# unitbase_Exodia.net
KiCad netlist of a schematic drawn in EAGLE
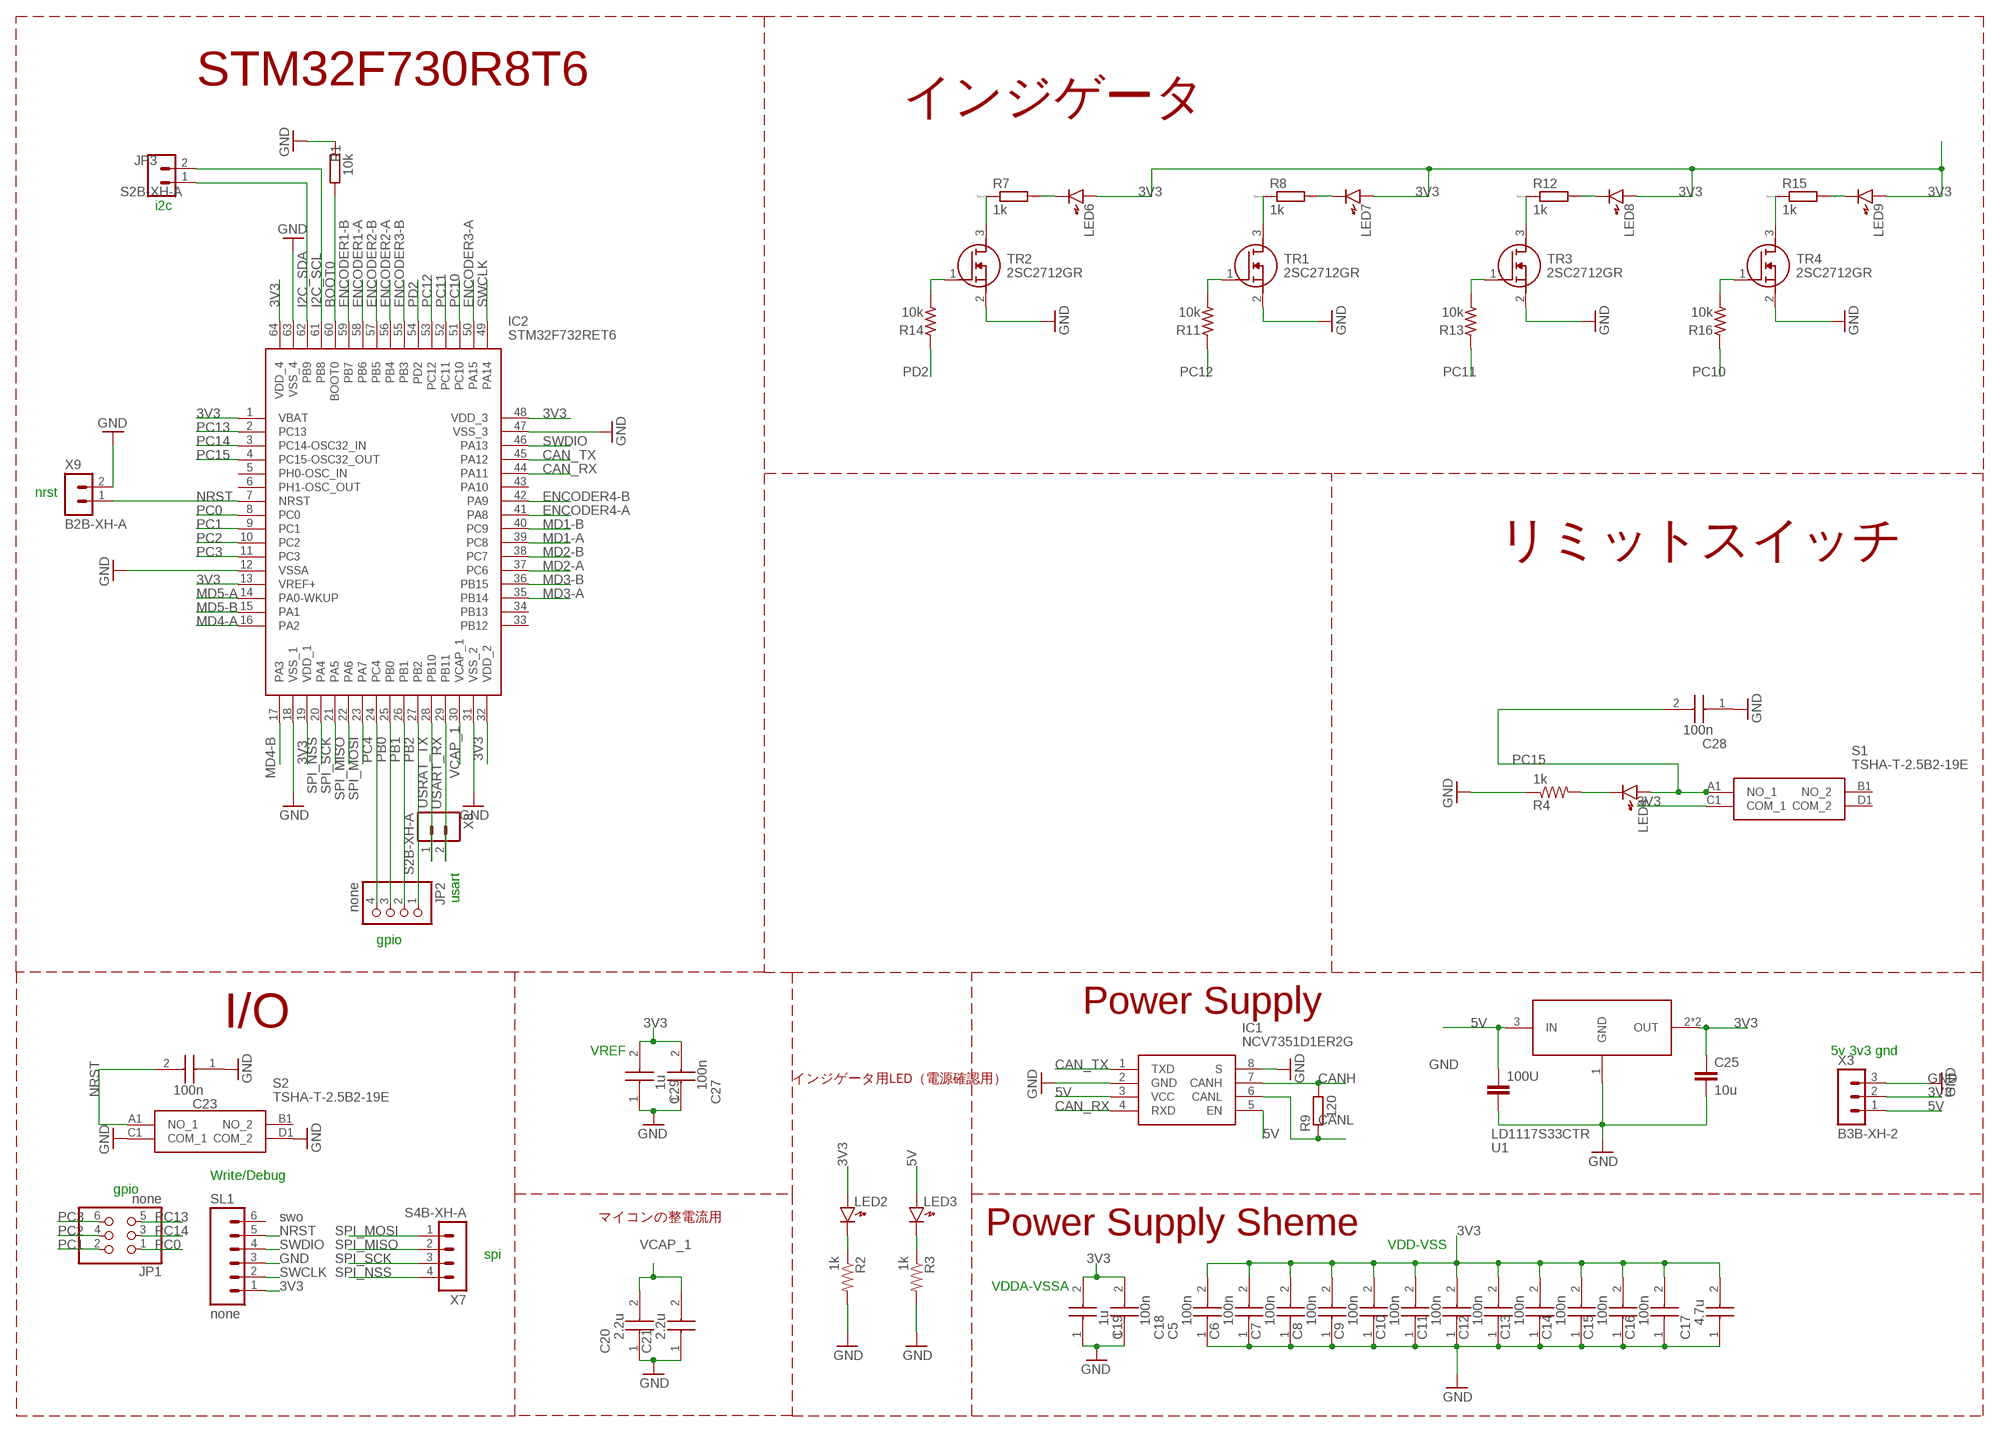
[diagram p0: schematic, sheet 1]
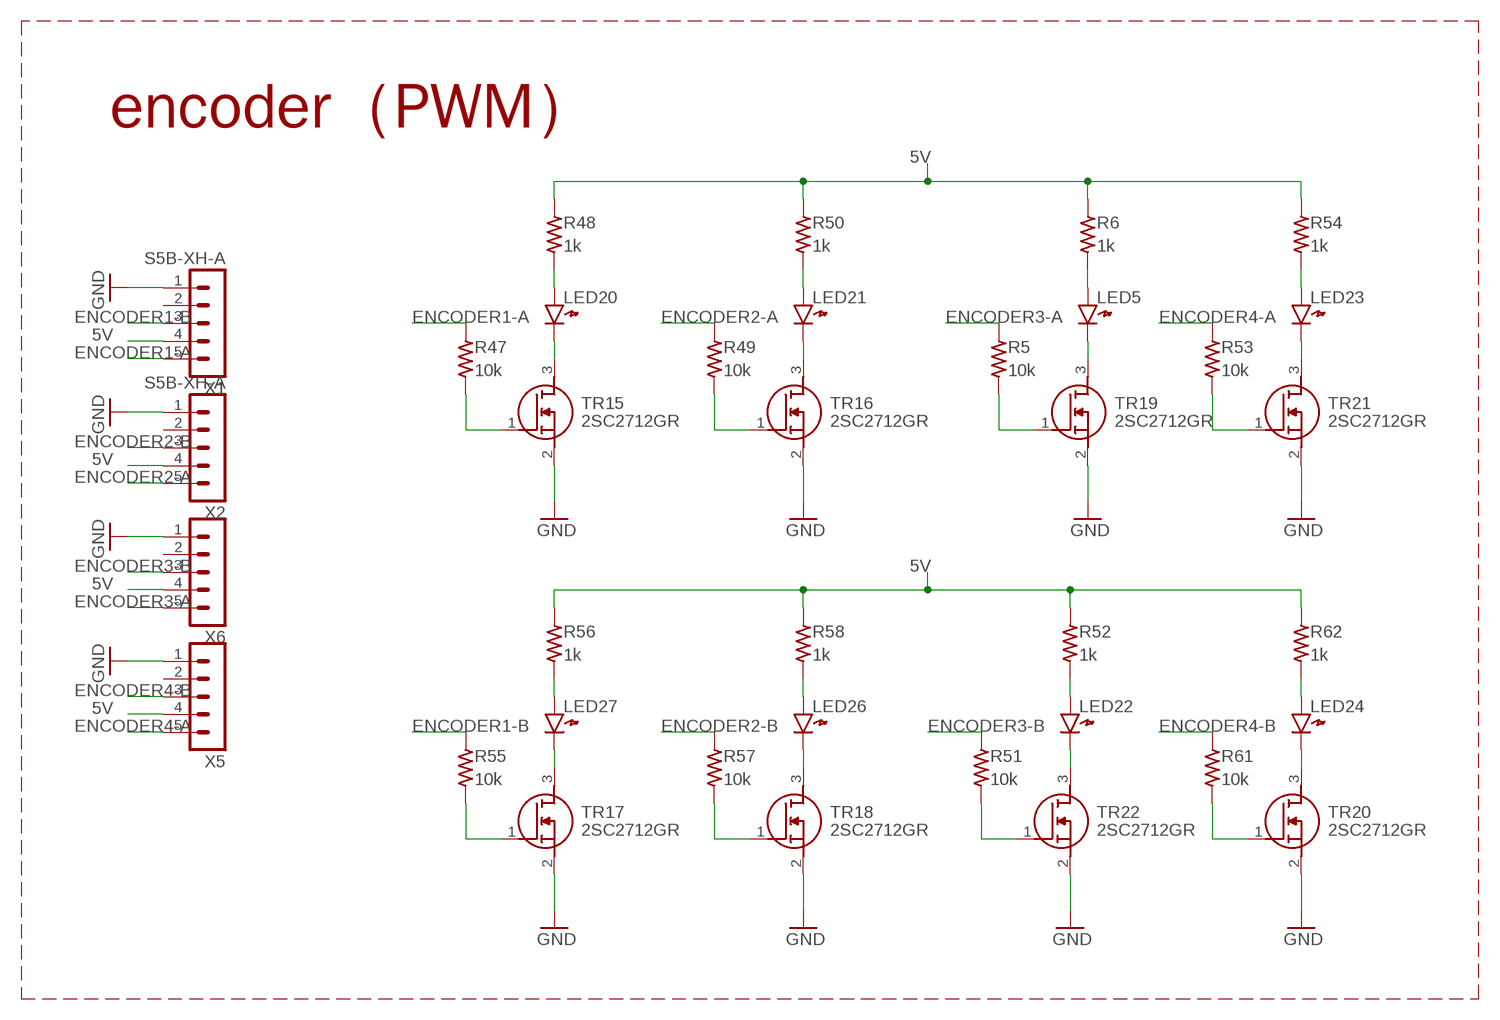
[diagram p1: schematic, sheet 2]
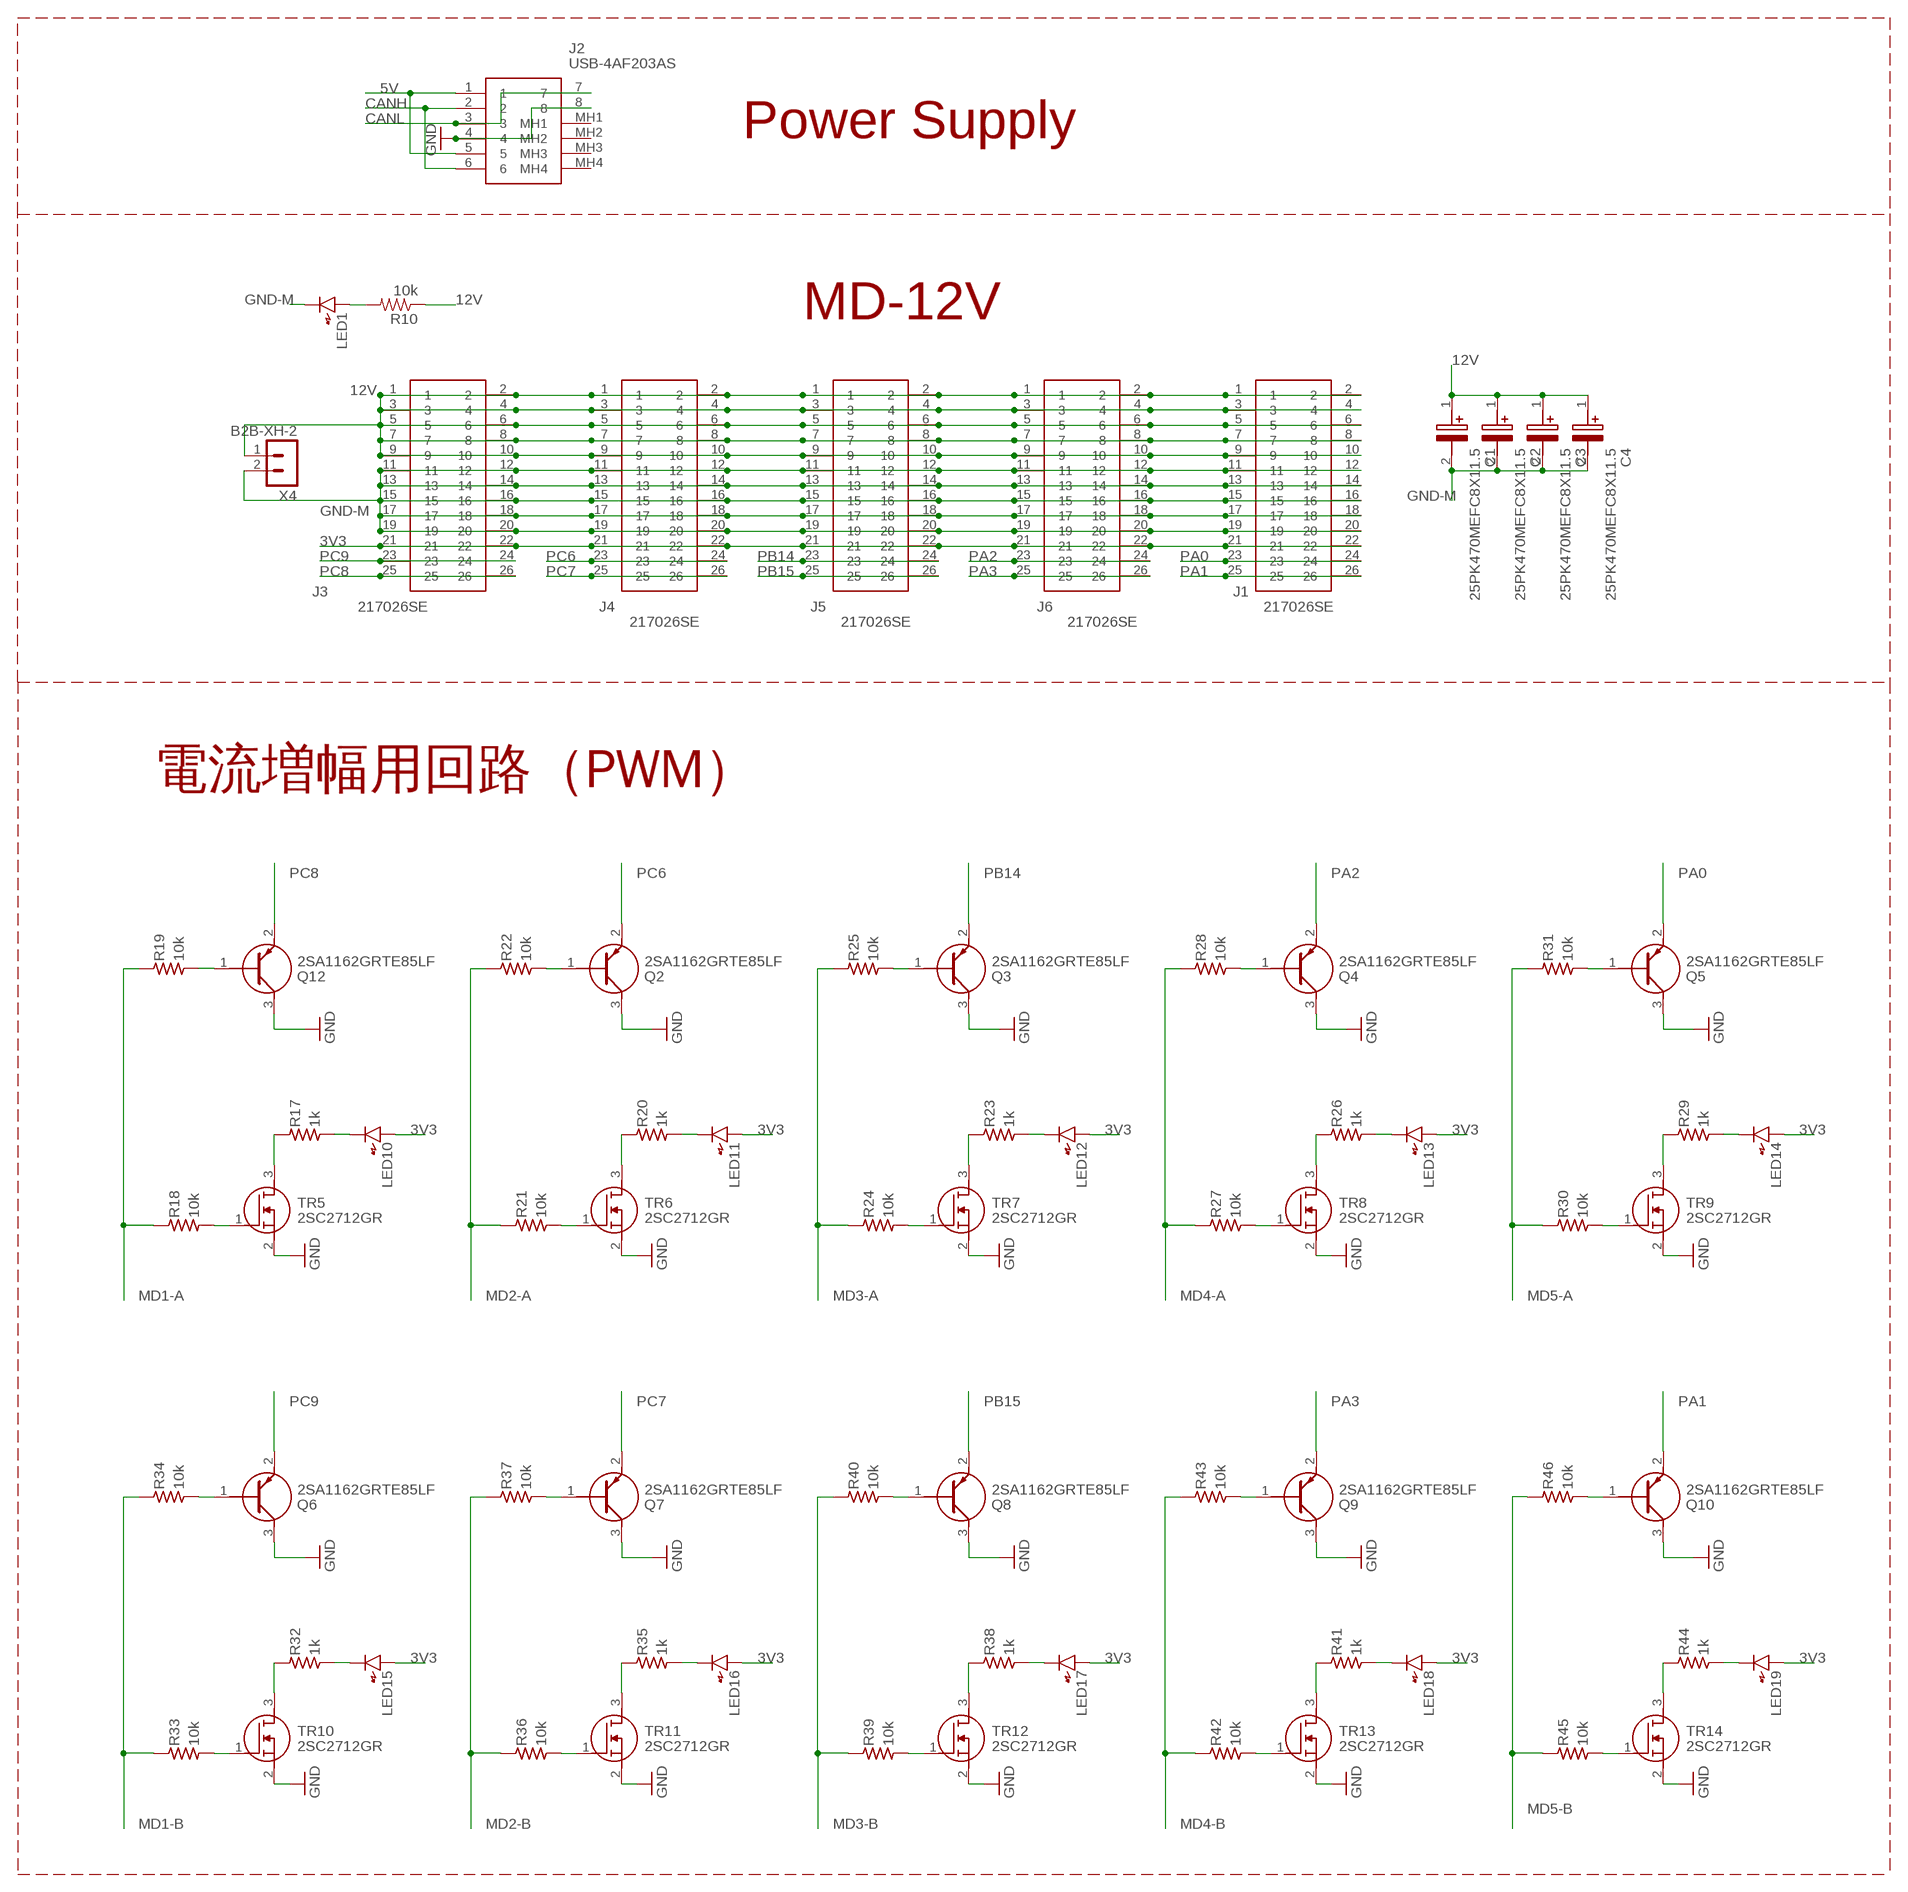
[diagram p2: schematic, sheet 3]

(export (version "E")
  (design (tool "Eeschema 10.0.6"))
  (components
    (comp (ref "LED5")
      (value "LED1608")
      (footprint "eagle-import:LED1608")
      (libsource (lib "eagle-import") (part "LED1608"))
    )
    (comp (ref "LED20")
      (value "LED1608")
      (footprint "eagle-import:LED1608")
      (libsource (lib "eagle-import") (part "LED1608"))
    )
    (comp (ref "LED21")
      (value "LED1608")
      (footprint "eagle-import:LED1608")
      (libsource (lib "eagle-import") (part "LED1608"))
    )
    (comp (ref "LED22")
      (value "LED1608")
      (footprint "eagle-import:LED1608")
      (libsource (lib "eagle-import") (part "LED1608"))
    )
    (comp (ref "LED23")
      (value "LED1608")
      (footprint "eagle-import:LED1608")
      (libsource (lib "eagle-import") (part "LED1608"))
    )
    (comp (ref "LED24")
      (value "LED1608")
      (footprint "eagle-import:LED1608")
      (libsource (lib "eagle-import") (part "LED1608"))
    )
    (comp (ref "LED26")
      (value "LED1608")
      (footprint "eagle-import:LED1608")
      (libsource (lib "eagle-import") (part "LED1608"))
    )
    (comp (ref "LED27")
      (value "LED1608")
      (footprint "eagle-import:LED1608")
      (libsource (lib "eagle-import") (part "LED1608"))
    )
    (comp (ref "R5")
      (value "10k")
      (footprint "eagle-import:SMD1608")
      (libsource (lib "eagle-import") (part "RESISTOR-US1608"))
    )
    (comp (ref "R6")
      (value "1k")
      (footprint "eagle-import:SMD1608")
      (libsource (lib "eagle-import") (part "RESISTOR-US1608"))
    )
    (comp (ref "R47")
      (value "10k")
      (footprint "eagle-import:SMD1608")
      (libsource (lib "eagle-import") (part "RESISTOR-US1608"))
    )
    (comp (ref "R48")
      (value "1k")
      (footprint "eagle-import:SMD1608")
      (libsource (lib "eagle-import") (part "RESISTOR-US1608"))
    )
    (comp (ref "R49")
      (value "10k")
      (footprint "eagle-import:SMD1608")
      (libsource (lib "eagle-import") (part "RESISTOR-US1608"))
    )
    (comp (ref "R50")
      (value "1k")
      (footprint "eagle-import:SMD1608")
      (libsource (lib "eagle-import") (part "RESISTOR-US1608"))
    )
    (comp (ref "R51")
      (value "10k")
      (footprint "eagle-import:SMD1608")
      (libsource (lib "eagle-import") (part "RESISTOR-US1608"))
    )
    (comp (ref "R52")
      (value "1k")
      (footprint "eagle-import:SMD1608")
      (libsource (lib "eagle-import") (part "RESISTOR-US1608"))
    )
    (comp (ref "R53")
      (value "10k")
      (footprint "eagle-import:SMD1608")
      (libsource (lib "eagle-import") (part "RESISTOR-US1608"))
    )
    (comp (ref "R54")
      (value "1k")
      (footprint "eagle-import:SMD1608")
      (libsource (lib "eagle-import") (part "RESISTOR-US1608"))
    )
    (comp (ref "R55")
      (value "10k")
      (footprint "eagle-import:SMD1608")
      (libsource (lib "eagle-import") (part "RESISTOR-US1608"))
    )
    (comp (ref "R56")
      (value "1k")
      (footprint "eagle-import:SMD1608")
      (libsource (lib "eagle-import") (part "RESISTOR-US1608"))
    )
    (comp (ref "R57")
      (value "10k")
      (footprint "eagle-import:SMD1608")
      (libsource (lib "eagle-import") (part "RESISTOR-US1608"))
    )
    (comp (ref "R58")
      (value "1k")
      (footprint "eagle-import:SMD1608")
      (libsource (lib "eagle-import") (part "RESISTOR-US1608"))
    )
    (comp (ref "R61")
      (value "10k")
      (footprint "eagle-import:SMD1608")
      (libsource (lib "eagle-import") (part "RESISTOR-US1608"))
    )
    (comp (ref "R62")
      (value "1k")
      (footprint "eagle-import:SMD1608")
      (libsource (lib "eagle-import") (part "RESISTOR-US1608"))
    )
    (comp (ref "TR15")
      (value "2SC2712GR")
      (footprint "eagle-import:SOT-23")
      (libsource (lib "eagle-import") (part "SOT-23_NMOS"))
    )
    (comp (ref "TR16")
      (value "2SC2712GR")
      (footprint "eagle-import:SOT-23")
      (libsource (lib "eagle-import") (part "SOT-23_NMOS"))
    )
    (comp (ref "TR17")
      (value "2SC2712GR")
      (footprint "eagle-import:SOT-23")
      (libsource (lib "eagle-import") (part "SOT-23_NMOS"))
    )
    (comp (ref "TR18")
      (value "2SC2712GR")
      (footprint "eagle-import:SOT-23")
      (libsource (lib "eagle-import") (part "SOT-23_NMOS"))
    )
    (comp (ref "TR19")
      (value "2SC2712GR")
      (footprint "eagle-import:SOT-23")
      (libsource (lib "eagle-import") (part "SOT-23_NMOS"))
    )
    (comp (ref "TR20")
      (value "2SC2712GR")
      (footprint "eagle-import:SOT-23")
      (libsource (lib "eagle-import") (part "SOT-23_NMOS"))
    )
    (comp (ref "TR21")
      (value "2SC2712GR")
      (footprint "eagle-import:SOT-23")
      (libsource (lib "eagle-import") (part "SOT-23_NMOS"))
    )
    (comp (ref "TR22")
      (value "2SC2712GR")
      (footprint "eagle-import:SOT-23")
      (libsource (lib "eagle-import") (part "SOT-23_NMOS"))
    )
    (comp (ref "X1")
      (value "S5B-XH-A")
      (footprint "eagle-import:S5B-XH-A")
      (libsource (lib "eagle-import") (part "S5B-XH-A"))
    )
    (comp (ref "X2")
      (value "S5B-XH-A")
      (footprint "eagle-import:S5B-XH-A")
      (libsource (lib "eagle-import") (part "S5B-XH-A"))
    )
    (comp (ref "X5")
      (value "S5B-XH-A")
      (footprint "eagle-import:S5B-XH-A")
      (libsource (lib "eagle-import") (part "S5B-XH-A"))
    )
    (comp (ref "X6")
      (value "S5B-XH-A")
      (footprint "eagle-import:S5B-XH-A")
      (libsource (lib "eagle-import") (part "S5B-XH-A"))
    )
    (comp (ref "100U")
      (value "100u")
      (footprint "eagle-import:C0603K")
      (libsource (lib "eagle-import") (part "C-EUC0603K"))
    )
    (comp (ref "C5")
      (value "100n")
      (footprint "eagle-import:CAPC1709X100N")
      (fields
        (field (name "MANUFACTURER_PART_NUMBER") "AMK107BBJ476MA-RE")
        (field (name "MOUSER_PART_NUMBER") "963-AMK107BBJ476MARE")
        (field (name "RS_PART_NUMBER") "1843762P")
      )
      (libsource (lib "eagle-import") (part "AMK107BBJ476MA-RE"))
    )
    (comp (ref "C6")
      (value "100n")
      (footprint "eagle-import:CAPC1709X100N")
      (fields
        (field (name "MANUFACTURER_PART_NUMBER") "AMK107BBJ476MA-RE")
        (field (name "MOUSER_PART_NUMBER") "963-AMK107BBJ476MARE")
        (field (name "RS_PART_NUMBER") "1843762P")
      )
      (libsource (lib "eagle-import") (part "AMK107BBJ476MA-RE"))
    )
    (comp (ref "C7")
      (value "100n")
      (footprint "eagle-import:CAPC1709X100N")
      (fields
        (field (name "MANUFACTURER_PART_NUMBER") "AMK107BBJ476MA-RE")
        (field (name "MOUSER_PART_NUMBER") "963-AMK107BBJ476MARE")
        (field (name "RS_PART_NUMBER") "1843762P")
      )
      (libsource (lib "eagle-import") (part "AMK107BBJ476MA-RE"))
    )
    (comp (ref "C8")
      (value "100n")
      (footprint "eagle-import:CAPC1709X100N")
      (fields
        (field (name "MANUFACTURER_PART_NUMBER") "AMK107BBJ476MA-RE")
        (field (name "MOUSER_PART_NUMBER") "963-AMK107BBJ476MARE")
        (field (name "RS_PART_NUMBER") "1843762P")
      )
      (libsource (lib "eagle-import") (part "AMK107BBJ476MA-RE"))
    )
    (comp (ref "C9")
      (value "100n")
      (footprint "eagle-import:CAPC1709X100N")
      (fields
        (field (name "MANUFACTURER_PART_NUMBER") "AMK107BBJ476MA-RE")
        (field (name "MOUSER_PART_NUMBER") "963-AMK107BBJ476MARE")
        (field (name "RS_PART_NUMBER") "1843762P")
      )
      (libsource (lib "eagle-import") (part "AMK107BBJ476MA-RE"))
    )
    (comp (ref "C10")
      (value "100n")
      (footprint "eagle-import:CAPC1709X100N")
      (fields
        (field (name "MANUFACTURER_PART_NUMBER") "AMK107BBJ476MA-RE")
        (field (name "MOUSER_PART_NUMBER") "963-AMK107BBJ476MARE")
        (field (name "RS_PART_NUMBER") "1843762P")
      )
      (libsource (lib "eagle-import") (part "AMK107BBJ476MA-RE"))
    )
    (comp (ref "C11")
      (value "100n")
      (footprint "eagle-import:CAPC1709X100N")
      (fields
        (field (name "MANUFACTURER_PART_NUMBER") "AMK107BBJ476MA-RE")
        (field (name "MOUSER_PART_NUMBER") "963-AMK107BBJ476MARE")
        (field (name "RS_PART_NUMBER") "1843762P")
      )
      (libsource (lib "eagle-import") (part "AMK107BBJ476MA-RE"))
    )
    (comp (ref "C12")
      (value "100n")
      (footprint "eagle-import:CAPC1709X100N")
      (fields
        (field (name "MANUFACTURER_PART_NUMBER") "AMK107BBJ476MA-RE")
        (field (name "MOUSER_PART_NUMBER") "963-AMK107BBJ476MARE")
        (field (name "RS_PART_NUMBER") "1843762P")
      )
      (libsource (lib "eagle-import") (part "AMK107BBJ476MA-RE"))
    )
    (comp (ref "C13")
      (value "100n")
      (footprint "eagle-import:CAPC1709X100N")
      (fields
        (field (name "MANUFACTURER_PART_NUMBER") "AMK107BBJ476MA-RE")
        (field (name "MOUSER_PART_NUMBER") "963-AMK107BBJ476MARE")
        (field (name "RS_PART_NUMBER") "1843762P")
      )
      (libsource (lib "eagle-import") (part "AMK107BBJ476MA-RE"))
    )
    (comp (ref "C14")
      (value "100n")
      (footprint "eagle-import:CAPC1709X100N")
      (fields
        (field (name "MANUFACTURER_PART_NUMBER") "AMK107BBJ476MA-RE")
        (field (name "MOUSER_PART_NUMBER") "963-AMK107BBJ476MARE")
        (field (name "RS_PART_NUMBER") "1843762P")
      )
      (libsource (lib "eagle-import") (part "AMK107BBJ476MA-RE"))
    )
    (comp (ref "C15")
      (value "100n")
      (footprint "eagle-import:CAPC1709X100N")
      (fields
        (field (name "MANUFACTURER_PART_NUMBER") "AMK107BBJ476MA-RE")
        (field (name "MOUSER_PART_NUMBER") "963-AMK107BBJ476MARE")
        (field (name "RS_PART_NUMBER") "1843762P")
      )
      (libsource (lib "eagle-import") (part "AMK107BBJ476MA-RE"))
    )
    (comp (ref "C16")
      (value "100n")
      (footprint "eagle-import:CAPC1709X100N")
      (fields
        (field (name "MANUFACTURER_PART_NUMBER") "AMK107BBJ476MA-RE")
        (field (name "MOUSER_PART_NUMBER") "963-AMK107BBJ476MARE")
        (field (name "RS_PART_NUMBER") "1843762P")
      )
      (libsource (lib "eagle-import") (part "AMK107BBJ476MA-RE"))
    )
    (comp (ref "C17")
      (value "4.7u")
      (footprint "eagle-import:CAPC1709X100N")
      (fields
        (field (name "MANUFACTURER_PART_NUMBER") "AMK107BBJ476MA-RE")
        (field (name "MOUSER_PART_NUMBER") "963-AMK107BBJ476MARE")
        (field (name "RS_PART_NUMBER") "1843762P")
      )
      (libsource (lib "eagle-import") (part "AMK107BBJ476MA-RE"))
    )
    (comp (ref "C18")
      (value "100n")
      (footprint "eagle-import:CAPC1709X100N")
      (fields
        (field (name "MANUFACTURER_PART_NUMBER") "AMK107BBJ476MA-RE")
        (field (name "MOUSER_PART_NUMBER") "963-AMK107BBJ476MARE")
        (field (name "RS_PART_NUMBER") "1843762P")
      )
      (libsource (lib "eagle-import") (part "AMK107BBJ476MA-RE"))
    )
    (comp (ref "C19")
      (value "1u")
      (footprint "eagle-import:CAPC1709X100N")
      (fields
        (field (name "MANUFACTURER_PART_NUMBER") "AMK107BBJ476MA-RE")
        (field (name "MOUSER_PART_NUMBER") "963-AMK107BBJ476MARE")
        (field (name "RS_PART_NUMBER") "1843762P")
      )
      (libsource (lib "eagle-import") (part "AMK107BBJ476MA-RE"))
    )
    (comp (ref "C20")
      (value "2.2u")
      (footprint "eagle-import:CAPC1709X100N")
      (fields
        (field (name "MANUFACTURER_PART_NUMBER") "AMK107BBJ476MA-RE")
        (field (name "MOUSER_PART_NUMBER") "963-AMK107BBJ476MARE")
        (field (name "RS_PART_NUMBER") "1843762P")
      )
      (libsource (lib "eagle-import") (part "AMK107BBJ476MA-RE"))
    )
    (comp (ref "C21")
      (value "2.2u")
      (footprint "eagle-import:CAPC1709X100N")
      (fields
        (field (name "MANUFACTURER_PART_NUMBER") "AMK107BBJ476MA-RE")
        (field (name "MOUSER_PART_NUMBER") "963-AMK107BBJ476MARE")
        (field (name "RS_PART_NUMBER") "1843762P")
      )
      (libsource (lib "eagle-import") (part "AMK107BBJ476MA-RE"))
    )
    (comp (ref "C23")
      (value "100n")
      (footprint "eagle-import:CAPC1709X100N")
      (fields
        (field (name "MANUFACTURER_PART_NUMBER") "AMK107BBJ476MA-RE")
        (field (name "MOUSER_PART_NUMBER") "963-AMK107BBJ476MARE")
        (field (name "RS_PART_NUMBER") "1843762P")
      )
      (libsource (lib "eagle-import") (part "AMK107BBJ476MA-RE"))
    )
    (comp (ref "C25")
      (value "10u")
      (footprint "eagle-import:C0603K")
      (libsource (lib "eagle-import") (part "C-EUC0603K"))
    )
    (comp (ref "C27")
      (value "100n")
      (footprint "eagle-import:CAPC1709X100N")
      (fields
        (field (name "MANUFACTURER_PART_NUMBER") "AMK107BBJ476MA-RE")
        (field (name "MOUSER_PART_NUMBER") "963-AMK107BBJ476MARE")
        (field (name "RS_PART_NUMBER") "1843762P")
      )
      (libsource (lib "eagle-import") (part "AMK107BBJ476MA-RE"))
    )
    (comp (ref "C28")
      (value "100n")
      (footprint "eagle-import:CAPC1709X100N")
      (fields
        (field (name "MANUFACTURER_PART_NUMBER") "AMK107BBJ476MA-RE")
        (field (name "MOUSER_PART_NUMBER") "963-AMK107BBJ476MARE")
        (field (name "RS_PART_NUMBER") "1843762P")
      )
      (libsource (lib "eagle-import") (part "AMK107BBJ476MA-RE"))
    )
    (comp (ref "C29")
      (value "1u")
      (footprint "eagle-import:CAPC1709X100N")
      (fields
        (field (name "MANUFACTURER_PART_NUMBER") "AMK107BBJ476MA-RE")
        (field (name "MOUSER_PART_NUMBER") "963-AMK107BBJ476MARE")
        (field (name "RS_PART_NUMBER") "1843762P")
      )
      (libsource (lib "eagle-import") (part "AMK107BBJ476MA-RE"))
    )
    (comp (ref "IC1")
      (value "NCV7351D1ER2G")
      (footprint "eagle-import:SOIC127P600X175-8N")
      (fields (field (name "MOUSER_PART_NUMBER") "863-NCV7351D1ER2G"))
      (libsource (lib "eagle-import") (part "NCV7351D1ER2G"))
    )
    (comp (ref "IC2")
      (value "STM32F732RET6")
      (footprint "eagle-import:QFP50P1200X1200X160-64N")
      (fields (field (name "MOUSER_PART_NUMBER") "511-STM32F732RET6"))
      (libsource (lib "eagle-import") (part "STM32F732RET6"))
    )
    (comp (ref "JP1")
      (value "none")
      (footprint "eagle-import:2X03")
      (libsource (lib "eagle-import") (part "PINHD-2X3"))
    )
    (comp (ref "JP2")
      (value "none")
      (footprint "eagle-import:1X04")
      (libsource (lib "eagle-import") (part "PINHD-1X4"))
    )
    (comp (ref "JP3")
      (value "S2B-XH-A")
      (footprint "eagle-import:S2B-XH-A")
      (libsource (lib "eagle-import") (part "S2B-XH-A"))
    )
    (comp (ref "LED2")
      (value "LED1608")
      (footprint "eagle-import:LED1608")
      (libsource (lib "eagle-import") (part "LED1608"))
    )
    (comp (ref "LED3")
      (value "LED1608")
      (footprint "eagle-import:LED1608")
      (libsource (lib "eagle-import") (part "LED1608"))
    )
    (comp (ref "LED4")
      (value "LED1608")
      (footprint "eagle-import:LED1608")
      (libsource (lib "eagle-import") (part "LED1608"))
    )
    (comp (ref "LED6")
      (value "LED1608")
      (footprint "eagle-import:LED1608")
      (libsource (lib "eagle-import") (part "LED1608"))
    )
    (comp (ref "LED7")
      (value "LED1608")
      (footprint "eagle-import:LED1608")
      (libsource (lib "eagle-import") (part "LED1608"))
    )
    (comp (ref "LED8")
      (value "LED1608")
      (footprint "eagle-import:LED1608")
      (libsource (lib "eagle-import") (part "LED1608"))
    )
    (comp (ref "LED9")
      (value "LED1608")
      (footprint "eagle-import:LED1608")
      (libsource (lib "eagle-import") (part "LED1608"))
    )
    (comp (ref "R1")
      (value "10k")
      (footprint "eagle-import:1608")
      (libsource (lib "eagle-import") (part "R1608"))
    )
    (comp (ref "R2")
      (value "1k")
      (footprint "eagle-import:R0603")
      (libsource (lib "eagle-import") (part "R-US_R0603"))
    )
    (comp (ref "R3")
      (value "1k")
      (footprint "eagle-import:R0603")
      (libsource (lib "eagle-import") (part "R-US_R0603"))
    )
    (comp (ref "R4")
      (value "1k")
      (footprint "eagle-import:R0603")
      (libsource (lib "eagle-import") (part "R-US_R0603"))
    )
    (comp (ref "R7")
      (value "1k")
      (footprint "eagle-import:R0603")
      (libsource (lib "eagle-import") (part "RR0603"))
    )
    (comp (ref "R8")
      (value "1k")
      (footprint "eagle-import:R0603")
      (libsource (lib "eagle-import") (part "RR0603"))
    )
    (comp (ref "R9")
      (value "120")
      (footprint "eagle-import:1608")
      (libsource (lib "eagle-import") (part "R1608"))
    )
    (comp (ref "R11")
      (value "10k")
      (footprint "eagle-import:SMD1608")
      (libsource (lib "eagle-import") (part "RESISTOR-US1608"))
    )
    (comp (ref "R12")
      (value "1k")
      (footprint "eagle-import:R0603")
      (libsource (lib "eagle-import") (part "RR0603"))
    )
    (comp (ref "R13")
      (value "10k")
      (footprint "eagle-import:SMD1608")
      (libsource (lib "eagle-import") (part "RESISTOR-US1608"))
    )
    (comp (ref "R14")
      (value "10k")
      (footprint "eagle-import:SMD1608")
      (libsource (lib "eagle-import") (part "RESISTOR-US1608"))
    )
    (comp (ref "R15")
      (value "1k")
      (footprint "eagle-import:R0603")
      (libsource (lib "eagle-import") (part "RR0603"))
    )
    (comp (ref "R16")
      (value "10k")
      (footprint "eagle-import:SMD1608")
      (libsource (lib "eagle-import") (part "RESISTOR-US1608"))
    )
    (comp (ref "S1")
      (value "TSHA-T-2.5B2-19E")
      (footprint "eagle-import:TSHAT25B219E")
      (libsource (lib "eagle-import") (part "TSHA-T-2.5B2-19E"))
    )
    (comp (ref "S2")
      (value "TSHA-T-2.5B2-19E")
      (footprint "eagle-import:TSHAT25B219E")
      (libsource (lib "eagle-import") (part "TSHA-T-2.5B2-19E"))
    )
    (comp (ref "SL1")
      (value "none")
      (footprint "eagle-import:06PA")
      (libsource (lib "eagle-import") (part "MA06"))
    )
    (comp (ref "TR1")
      (value "2SC2712GR")
      (footprint "eagle-import:SOT-23")
      (libsource (lib "eagle-import") (part "SOT-23_NMOS"))
    )
    (comp (ref "TR2")
      (value "2SC2712GR")
      (footprint "eagle-import:SOT-23")
      (libsource (lib "eagle-import") (part "SOT-23_NMOS"))
    )
    (comp (ref "TR3")
      (value "2SC2712GR")
      (footprint "eagle-import:SOT-23")
      (libsource (lib "eagle-import") (part "SOT-23_NMOS"))
    )
    (comp (ref "TR4")
      (value "2SC2712GR")
      (footprint "eagle-import:SOT-23")
      (libsource (lib "eagle-import") (part "SOT-23_NMOS"))
    )
    (comp (ref "U1")
      (value "LD1117S33CTR")
      (footprint "eagle-import:SOT223")
      (fields (field (name "MF") "STMicroelectronics"))
      (libsource (lib "eagle-import") (part "LD1117S33CTR"))
    )
    (comp (ref "X3")
      (value "B3B-XH-2")
      (footprint "eagle-import:B3B-XH-A")
      (libsource (lib "eagle-import") (part "B3B-XH-2"))
    )
    (comp (ref "X7")
      (value "S4B-XH-A")
      (footprint "eagle-import:S4B-XH-A")
      (libsource (lib "eagle-import") (part "S4B-XH-A"))
    )
    (comp (ref "X8")
      (value "S2B-XH-A")
      (footprint "eagle-import:S2B-XH-A")
      (libsource (lib "eagle-import") (part "S2B-XH-A"))
    )
    (comp (ref "X9")
      (value "B2B-XH-A")
      (footprint "eagle-import:B2B-XH-A")
      (libsource (lib "eagle-import") (part "B2B-XH-A"))
    )
    (comp (ref "C1")
      (value "25PK470MEFC8X11.5")
      (footprint "eagle-import:CAPPRD350W60D825H1150")
      (fields (field (name "MOUSER_PART_NUMBER") "232-25PK470MEFC8X115"))
      (libsource (lib "eagle-import") (part "25PK470MEFC8X11.5"))
    )
    (comp (ref "C2")
      (value "25PK470MEFC8X11.5")
      (footprint "eagle-import:CAPPRD350W60D825H1150")
      (fields (field (name "MOUSER_PART_NUMBER") "232-25PK470MEFC8X115"))
      (libsource (lib "eagle-import") (part "25PK470MEFC8X11.5"))
    )
    (comp (ref "C3")
      (value "25PK470MEFC8X11.5")
      (footprint "eagle-import:CAPPRD350W60D825H1150")
      (fields (field (name "MOUSER_PART_NUMBER") "232-25PK470MEFC8X115"))
      (libsource (lib "eagle-import") (part "25PK470MEFC8X11.5"))
    )
    (comp (ref "C4")
      (value "25PK470MEFC8X11.5")
      (footprint "eagle-import:CAPPRD350W60D825H1150")
      (fields (field (name "MOUSER_PART_NUMBER") "232-25PK470MEFC8X115"))
      (libsource (lib "eagle-import") (part "25PK470MEFC8X11.5"))
    )
    (comp (ref "J1")
      (value "217026SE")
      (footprint "eagle-import:217026SE")
      (libsource (lib "eagle-import") (part "217026SE"))
    )
    (comp (ref "J2")
      (value "USB-4AF203AS")
      (footprint "eagle-import:USB4AF203AS")
      (libsource (lib "eagle-import") (part "USB-4AF203AS"))
    )
    (comp (ref "J3")
      (value "217026SE")
      (footprint "eagle-import:217026SE")
      (libsource (lib "eagle-import") (part "217026SE"))
    )
    (comp (ref "J4")
      (value "217026SE")
      (footprint "eagle-import:217026SE")
      (libsource (lib "eagle-import") (part "217026SE"))
    )
    (comp (ref "J5")
      (value "217026SE")
      (footprint "eagle-import:217026SE")
      (libsource (lib "eagle-import") (part "217026SE"))
    )
    (comp (ref "J6")
      (value "217026SE")
      (footprint "eagle-import:217026SE")
      (libsource (lib "eagle-import") (part "217026SE"))
    )
    (comp (ref "LED1")
      (value "LED1608")
      (footprint "eagle-import:LED1608")
      (libsource (lib "eagle-import") (part "LED1608"))
    )
    (comp (ref "LED10")
      (value "LED1608")
      (footprint "eagle-import:LED1608")
      (libsource (lib "eagle-import") (part "LED1608"))
    )
    (comp (ref "LED11")
      (value "LED1608")
      (footprint "eagle-import:LED1608")
      (libsource (lib "eagle-import") (part "LED1608"))
    )
    (comp (ref "LED12")
      (value "LED1608")
      (footprint "eagle-import:LED1608")
      (libsource (lib "eagle-import") (part "LED1608"))
    )
    (comp (ref "LED13")
      (value "LED1608")
      (footprint "eagle-import:LED1608")
      (libsource (lib "eagle-import") (part "LED1608"))
    )
    (comp (ref "LED14")
      (value "LED1608")
      (footprint "eagle-import:LED1608")
      (libsource (lib "eagle-import") (part "LED1608"))
    )
    (comp (ref "LED15")
      (value "LED1608")
      (footprint "eagle-import:LED1608")
      (libsource (lib "eagle-import") (part "LED1608"))
    )
    (comp (ref "LED16")
      (value "LED1608")
      (footprint "eagle-import:LED1608")
      (libsource (lib "eagle-import") (part "LED1608"))
    )
    (comp (ref "LED17")
      (value "LED1608")
      (footprint "eagle-import:LED1608")
      (libsource (lib "eagle-import") (part "LED1608"))
    )
    (comp (ref "LED18")
      (value "LED1608")
      (footprint "eagle-import:LED1608")
      (libsource (lib "eagle-import") (part "LED1608"))
    )
    (comp (ref "LED19")
      (value "LED1608")
      (footprint "eagle-import:LED1608")
      (libsource (lib "eagle-import") (part "LED1608"))
    )
    (comp (ref "Q2")
      (value "2SA1162GRTE85LF")
      (footprint "eagle-import:2SA1162GRTE85LF")
      (libsource (lib "eagle-import") (part "2SA1162GRTE85LF"))
    )
    (comp (ref "Q3")
      (value "2SA1162GRTE85LF")
      (footprint "eagle-import:2SA1162GRTE85LF")
      (libsource (lib "eagle-import") (part "2SA1162GRTE85LF"))
    )
    (comp (ref "Q4")
      (value "2SA1162GRTE85LF")
      (footprint "eagle-import:2SA1162GRTE85LF")
      (libsource (lib "eagle-import") (part "2SA1162GRTE85LF"))
    )
    (comp (ref "Q5")
      (value "2SA1162GRTE85LF")
      (footprint "eagle-import:2SA1162GRTE85LF")
      (libsource (lib "eagle-import") (part "2SA1162GRTE85LF"))
    )
    (comp (ref "Q6")
      (value "2SA1162GRTE85LF")
      (footprint "eagle-import:2SA1162GRTE85LF")
      (libsource (lib "eagle-import") (part "2SA1162GRTE85LF"))
    )
    (comp (ref "Q7")
      (value "2SA1162GRTE85LF")
      (footprint "eagle-import:2SA1162GRTE85LF")
      (libsource (lib "eagle-import") (part "2SA1162GRTE85LF"))
    )
    (comp (ref "Q8")
      (value "2SA1162GRTE85LF")
      (footprint "eagle-import:2SA1162GRTE85LF")
      (libsource (lib "eagle-import") (part "2SA1162GRTE85LF"))
    )
    (comp (ref "Q9")
      (value "2SA1162GRTE85LF")
      (footprint "eagle-import:2SA1162GRTE85LF")
      (libsource (lib "eagle-import") (part "2SA1162GRTE85LF"))
    )
    (comp (ref "Q10")
      (value "2SA1162GRTE85LF")
      (footprint "eagle-import:2SA1162GRTE85LF")
      (libsource (lib "eagle-import") (part "2SA1162GRTE85LF"))
    )
    (comp (ref "Q12")
      (value "2SA1162GRTE85LF")
      (footprint "eagle-import:2SA1162GRTE85LF")
      (libsource (lib "eagle-import") (part "2SA1162GRTE85LF"))
    )
    (comp (ref "R10")
      (value "10k")
      (footprint "eagle-import:R0603")
      (libsource (lib "eagle-import") (part "R-US_R0603"))
    )
    (comp (ref "R17")
      (value "1k")
      (footprint "eagle-import:SMD1608")
      (libsource (lib "eagle-import") (part "RESISTOR-US1608"))
    )
    (comp (ref "R18")
      (value "10k")
      (footprint "eagle-import:SMD1608")
      (libsource (lib "eagle-import") (part "RESISTOR-US1608"))
    )
    (comp (ref "R19")
      (value "10k")
      (footprint "eagle-import:SMD1608")
      (libsource (lib "eagle-import") (part "RESISTOR-US1608"))
    )
    (comp (ref "R20")
      (value "1k")
      (footprint "eagle-import:SMD1608")
      (libsource (lib "eagle-import") (part "RESISTOR-US1608"))
    )
    (comp (ref "R21")
      (value "10k")
      (footprint "eagle-import:SMD1608")
      (libsource (lib "eagle-import") (part "RESISTOR-US1608"))
    )
    (comp (ref "R22")
      (value "10k")
      (footprint "eagle-import:SMD1608")
      (libsource (lib "eagle-import") (part "RESISTOR-US1608"))
    )
    (comp (ref "R23")
      (value "1k")
      (footprint "eagle-import:SMD1608")
      (libsource (lib "eagle-import") (part "RESISTOR-US1608"))
    )
    (comp (ref "R24")
      (value "10k")
      (footprint "eagle-import:SMD1608")
      (libsource (lib "eagle-import") (part "RESISTOR-US1608"))
    )
    (comp (ref "R25")
      (value "10k")
      (footprint "eagle-import:SMD1608")
      (libsource (lib "eagle-import") (part "RESISTOR-US1608"))
    )
    (comp (ref "R26")
      (value "1k")
      (footprint "eagle-import:SMD1608")
      (libsource (lib "eagle-import") (part "RESISTOR-US1608"))
    )
    (comp (ref "R27")
      (value "10k")
      (footprint "eagle-import:SMD1608")
      (libsource (lib "eagle-import") (part "RESISTOR-US1608"))
    )
    (comp (ref "R28")
      (value "10k")
      (footprint "eagle-import:SMD1608")
      (libsource (lib "eagle-import") (part "RESISTOR-US1608"))
    )
    (comp (ref "R29")
      (value "1k")
      (footprint "eagle-import:SMD1608")
      (libsource (lib "eagle-import") (part "RESISTOR-US1608"))
    )
    (comp (ref "R30")
      (value "10k")
      (footprint "eagle-import:SMD1608")
      (libsource (lib "eagle-import") (part "RESISTOR-US1608"))
    )
    (comp (ref "R31")
      (value "10k")
      (footprint "eagle-import:SMD1608")
      (libsource (lib "eagle-import") (part "RESISTOR-US1608"))
    )
    (comp (ref "R32")
      (value "1k")
      (footprint "eagle-import:SMD1608")
      (libsource (lib "eagle-import") (part "RESISTOR-US1608"))
    )
    (comp (ref "R33")
      (value "10k")
      (footprint "eagle-import:SMD1608")
      (libsource (lib "eagle-import") (part "RESISTOR-US1608"))
    )
    (comp (ref "R34")
      (value "10k")
      (footprint "eagle-import:SMD1608")
      (libsource (lib "eagle-import") (part "RESISTOR-US1608"))
    )
    (comp (ref "R35")
      (value "1k")
      (footprint "eagle-import:SMD1608")
      (libsource (lib "eagle-import") (part "RESISTOR-US1608"))
    )
    (comp (ref "R36")
      (value "10k")
      (footprint "eagle-import:SMD1608")
      (libsource (lib "eagle-import") (part "RESISTOR-US1608"))
    )
    (comp (ref "R37")
      (value "10k")
      (footprint "eagle-import:SMD1608")
      (libsource (lib "eagle-import") (part "RESISTOR-US1608"))
    )
    (comp (ref "R38")
      (value "1k")
      (footprint "eagle-import:SMD1608")
      (libsource (lib "eagle-import") (part "RESISTOR-US1608"))
    )
    (comp (ref "R39")
      (value "10k")
      (footprint "eagle-import:SMD1608")
      (libsource (lib "eagle-import") (part "RESISTOR-US1608"))
    )
    (comp (ref "R40")
      (value "10k")
      (footprint "eagle-import:SMD1608")
      (libsource (lib "eagle-import") (part "RESISTOR-US1608"))
    )
    (comp (ref "R41")
      (value "1k")
      (footprint "eagle-import:SMD1608")
      (libsource (lib "eagle-import") (part "RESISTOR-US1608"))
    )
    (comp (ref "R42")
      (value "10k")
      (footprint "eagle-import:SMD1608")
      (libsource (lib "eagle-import") (part "RESISTOR-US1608"))
    )
    (comp (ref "R43")
      (value "10k")
      (footprint "eagle-import:SMD1608")
      (libsource (lib "eagle-import") (part "RESISTOR-US1608"))
    )
    (comp (ref "R44")
      (value "1k")
      (footprint "eagle-import:SMD1608")
      (libsource (lib "eagle-import") (part "RESISTOR-US1608"))
    )
    (comp (ref "R45")
      (value "10k")
      (footprint "eagle-import:SMD1608")
      (libsource (lib "eagle-import") (part "RESISTOR-US1608"))
    )
    (comp (ref "R46")
      (value "10k")
      (footprint "eagle-import:SMD1608")
      (libsource (lib "eagle-import") (part "RESISTOR-US1608"))
    )
    (comp (ref "TR5")
      (value "2SC2712GR")
      (footprint "eagle-import:SOT-23")
      (libsource (lib "eagle-import") (part "SOT-23_NMOS"))
    )
    (comp (ref "TR6")
      (value "2SC2712GR")
      (footprint "eagle-import:SOT-23")
      (libsource (lib "eagle-import") (part "SOT-23_NMOS"))
    )
    (comp (ref "TR7")
      (value "2SC2712GR")
      (footprint "eagle-import:SOT-23")
      (libsource (lib "eagle-import") (part "SOT-23_NMOS"))
    )
    (comp (ref "TR8")
      (value "2SC2712GR")
      (footprint "eagle-import:SOT-23")
      (libsource (lib "eagle-import") (part "SOT-23_NMOS"))
    )
    (comp (ref "TR9")
      (value "2SC2712GR")
      (footprint "eagle-import:SOT-23")
      (libsource (lib "eagle-import") (part "SOT-23_NMOS"))
    )
    (comp (ref "TR10")
      (value "2SC2712GR")
      (footprint "eagle-import:SOT-23")
      (libsource (lib "eagle-import") (part "SOT-23_NMOS"))
    )
    (comp (ref "TR11")
      (value "2SC2712GR")
      (footprint "eagle-import:SOT-23")
      (libsource (lib "eagle-import") (part "SOT-23_NMOS"))
    )
    (comp (ref "TR12")
      (value "2SC2712GR")
      (footprint "eagle-import:SOT-23")
      (libsource (lib "eagle-import") (part "SOT-23_NMOS"))
    )
    (comp (ref "TR13")
      (value "2SC2712GR")
      (footprint "eagle-import:SOT-23")
      (libsource (lib "eagle-import") (part "SOT-23_NMOS"))
    )
    (comp (ref "TR14")
      (value "2SC2712GR")
      (footprint "eagle-import:SOT-23")
      (libsource (lib "eagle-import") (part "SOT-23_NMOS"))
    )
    (comp (ref "X4")
      (value "B2B-XH-2")
      (footprint "eagle-import:B2B-XH-A")
      (libsource (lib "eagle-import") (part "B2B-XH-2"))
    )
  )
  (nets
    (net (code "1") (name "3V3") (class "Default")
      (node (ref "C10") (pin "2") (pinfunction "2_2") (pintype "bidirectional"))
      (node (ref "C11") (pin "2") (pinfunction "2_2") (pintype "bidirectional"))
      (node (ref "C12") (pin "2") (pinfunction "2_2") (pintype "bidirectional"))
      (node (ref "C13") (pin "2") (pinfunction "2_2") (pintype "bidirectional"))
      (node (ref "C14") (pin "2") (pinfunction "2_2") (pintype "bidirectional"))
      (node (ref "C15") (pin "2") (pinfunction "2_2") (pintype "bidirectional"))
      (node (ref "C16") (pin "2") (pinfunction "2_2") (pintype "bidirectional"))
      (node (ref "C17") (pin "2") (pinfunction "2_2") (pintype "bidirectional"))
      (node (ref "C18") (pin "2") (pinfunction "2_2") (pintype "bidirectional"))
      (node (ref "C19") (pin "2") (pinfunction "2_2") (pintype "bidirectional"))
      (node (ref "C25") (pin "1") (pinfunction "1_1") (pintype "passive"))
      (node (ref "C27") (pin "2") (pinfunction "2_2") (pintype "bidirectional"))
      (node (ref "C29") (pin "2") (pinfunction "2_2") (pintype "bidirectional"))
      (node (ref "C5") (pin "2") (pinfunction "2_2") (pintype "bidirectional"))
      (node (ref "C6") (pin "2") (pinfunction "2_2") (pintype "bidirectional"))
      (node (ref "C7") (pin "2") (pinfunction "2_2") (pintype "bidirectional"))
      (node (ref "C8") (pin "2") (pinfunction "2_2") (pintype "bidirectional"))
      (node (ref "C9") (pin "2") (pinfunction "2_2") (pintype "bidirectional"))
      (node (ref "IC2") (pin "1") (pinfunction "VBAT_1") (pintype "power_in"))
      (node (ref "IC2") (pin "13") (pinfunction "VREF+_13") (pintype "power_in"))
      (node (ref "IC2") (pin "19") (pinfunction "VDD_1_19") (pintype "power_in"))
      (node (ref "IC2") (pin "32") (pinfunction "VDD_2_32") (pintype "power_in"))
      (node (ref "IC2") (pin "48") (pinfunction "VDD_3_48") (pintype "power_in"))
      (node (ref "IC2") (pin "64") (pinfunction "VDD_4_64") (pintype "power_in"))
      (node (ref "J1") (pin "21") (pinfunction "21_21") (pintype "bidirectional"))
      (node (ref "J1") (pin "22") (pinfunction "22_22") (pintype "bidirectional"))
      (node (ref "J3") (pin "21") (pinfunction "21_21") (pintype "bidirectional"))
      (node (ref "J3") (pin "22") (pinfunction "22_22") (pintype "bidirectional"))
      (node (ref "J4") (pin "21") (pinfunction "21_21") (pintype "bidirectional"))
      (node (ref "J4") (pin "22") (pinfunction "22_22") (pintype "bidirectional"))
      (node (ref "J5") (pin "21") (pinfunction "21_21") (pintype "bidirectional"))
      (node (ref "J5") (pin "22") (pinfunction "22_22") (pintype "bidirectional"))
      (node (ref "J6") (pin "21") (pinfunction "21_21") (pintype "bidirectional"))
      (node (ref "J6") (pin "22") (pinfunction "22_22") (pintype "bidirectional"))
      (node (ref "LED10") (pin "A") (pinfunction "A_A") (pintype "passive"))
      (node (ref "LED11") (pin "A") (pinfunction "A_A") (pintype "passive"))
      (node (ref "LED12") (pin "A") (pinfunction "A_A") (pintype "passive"))
      (node (ref "LED13") (pin "A") (pinfunction "A_A") (pintype "passive"))
      (node (ref "LED14") (pin "A") (pinfunction "A_A") (pintype "passive"))
      (node (ref "LED15") (pin "A") (pinfunction "A_A") (pintype "passive"))
      (node (ref "LED16") (pin "A") (pinfunction "A_A") (pintype "passive"))
      (node (ref "LED17") (pin "A") (pinfunction "A_A") (pintype "passive"))
      (node (ref "LED18") (pin "A") (pinfunction "A_A") (pintype "passive"))
      (node (ref "LED19") (pin "A") (pinfunction "A_A") (pintype "passive"))
      (node (ref "LED2") (pin "A") (pinfunction "A_A") (pintype "passive"))
      (node (ref "LED6") (pin "A") (pinfunction "A_A") (pintype "passive"))
      (node (ref "LED7") (pin "A") (pinfunction "A_A") (pintype "passive"))
      (node (ref "LED8") (pin "A") (pinfunction "A_A") (pintype "passive"))
      (node (ref "LED9") (pin "A") (pinfunction "A_A") (pintype "passive"))
      (node (ref "S1") (pin "C1") (pinfunction "COM_1_C1") (pintype "bidirectional"))
      (node (ref "SL1") (pin "1") (pinfunction "1_1") (pintype "passive"))
      (node (ref "U1") (pin "2") (pinfunction "OUT_2") (pintype "output"))
      (node (ref "U1") (pin "4") (pinfunction "OUT_4") (pintype "output"))
      (node (ref "X3") (pin "2") (pinfunction "2_2") (pintype "passive"))
    )
    (net (code "2") (name "5V") (class "Default")
      (node (ref "100U") (pin "1") (pinfunction "1_1") (pintype "passive"))
      (node (ref "IC1") (pin "3") (pinfunction "VCC_3") (pintype "bidirectional"))
      (node (ref "IC1") (pin "5") (pinfunction "EN_5") (pintype "bidirectional"))
      (node (ref "J2") (pin "1") (pinfunction "1_1") (pintype "bidirectional"))
      (node (ref "J2") (pin "5") (pinfunction "5_5") (pintype "bidirectional"))
      (node (ref "LED3") (pin "A") (pinfunction "A_A") (pintype "passive"))
      (node (ref "R48") (pin "1") (pinfunction "1_1") (pintype "passive"))
      (node (ref "R50") (pin "1") (pinfunction "1_1") (pintype "passive"))
      (node (ref "R52") (pin "1") (pinfunction "1_1") (pintype "passive"))
      (node (ref "R54") (pin "1") (pinfunction "1_1") (pintype "passive"))
      (node (ref "R56") (pin "1") (pinfunction "1_1") (pintype "passive"))
      (node (ref "R58") (pin "1") (pinfunction "1_1") (pintype "passive"))
      (node (ref "R6") (pin "1") (pinfunction "1_1") (pintype "passive"))
      (node (ref "R62") (pin "1") (pinfunction "1_1") (pintype "passive"))
      (node (ref "U1") (pin "3") (pinfunction "IN_3") (pintype "input"))
      (node (ref "X1") (pin "4") (pinfunction "4_4") (pintype "passive"))
      (node (ref "X2") (pin "4") (pinfunction "4_4") (pintype "passive"))
      (node (ref "X3") (pin "1") (pinfunction "1_1") (pintype "passive"))
      (node (ref "X5") (pin "4") (pinfunction "4_4") (pintype "passive"))
      (node (ref "X6") (pin "4") (pinfunction "4_4") (pintype "passive"))
    )
    (net (code "3") (name "12V") (class "Default")
      (node (ref "C1") (pin "1") (pinfunction "+_1") (pintype "bidirectional"))
      (node (ref "C2") (pin "1") (pinfunction "+_1") (pintype "bidirectional"))
      (node (ref "C3") (pin "1") (pinfunction "+_1") (pintype "bidirectional"))
      (node (ref "C4") (pin "1") (pinfunction "+_1") (pintype "bidirectional"))
      (node (ref "J1") (pin "1") (pinfunction "1_1") (pintype "bidirectional"))
      (node (ref "J1") (pin "10") (pinfunction "10_10") (pintype "bidirectional"))
      (node (ref "J1") (pin "2") (pinfunction "2_2") (pintype "bidirectional"))
      (node (ref "J1") (pin "3") (pinfunction "3_3") (pintype "bidirectional"))
      (node (ref "J1") (pin "4") (pinfunction "4_4") (pintype "bidirectional"))
      (node (ref "J1") (pin "5") (pinfunction "5_5") (pintype "bidirectional"))
      (node (ref "J1") (pin "6") (pinfunction "6_6") (pintype "bidirectional"))
      (node (ref "J1") (pin "7") (pinfunction "7_7") (pintype "bidirectional"))
      (node (ref "J1") (pin "8") (pinfunction "8_8") (pintype "bidirectional"))
      (node (ref "J1") (pin "9") (pinfunction "9_9") (pintype "bidirectional"))
      (node (ref "J3") (pin "1") (pinfunction "1_1") (pintype "bidirectional"))
      (node (ref "J3") (pin "10") (pinfunction "10_10") (pintype "bidirectional"))
      (node (ref "J3") (pin "2") (pinfunction "2_2") (pintype "bidirectional"))
      (node (ref "J3") (pin "3") (pinfunction "3_3") (pintype "bidirectional"))
      (node (ref "J3") (pin "4") (pinfunction "4_4") (pintype "bidirectional"))
      (node (ref "J3") (pin "5") (pinfunction "5_5") (pintype "bidirectional"))
      (node (ref "J3") (pin "6") (pinfunction "6_6") (pintype "bidirectional"))
      (node (ref "J3") (pin "7") (pinfunction "7_7") (pintype "bidirectional"))
      (node (ref "J3") (pin "8") (pinfunction "8_8") (pintype "bidirectional"))
      (node (ref "J3") (pin "9") (pinfunction "9_9") (pintype "bidirectional"))
      (node (ref "J4") (pin "1") (pinfunction "1_1") (pintype "bidirectional"))
      (node (ref "J4") (pin "10") (pinfunction "10_10") (pintype "bidirectional"))
      (node (ref "J4") (pin "2") (pinfunction "2_2") (pintype "bidirectional"))
      (node (ref "J4") (pin "3") (pinfunction "3_3") (pintype "bidirectional"))
      (node (ref "J4") (pin "4") (pinfunction "4_4") (pintype "bidirectional"))
      (node (ref "J4") (pin "5") (pinfunction "5_5") (pintype "bidirectional"))
      (node (ref "J4") (pin "6") (pinfunction "6_6") (pintype "bidirectional"))
      (node (ref "J4") (pin "7") (pinfunction "7_7") (pintype "bidirectional"))
      (node (ref "J4") (pin "8") (pinfunction "8_8") (pintype "bidirectional"))
      (node (ref "J4") (pin "9") (pinfunction "9_9") (pintype "bidirectional"))
      (node (ref "J5") (pin "1") (pinfunction "1_1") (pintype "bidirectional"))
      (node (ref "J5") (pin "10") (pinfunction "10_10") (pintype "bidirectional"))
      (node (ref "J5") (pin "2") (pinfunction "2_2") (pintype "bidirectional"))
      (node (ref "J5") (pin "3") (pinfunction "3_3") (pintype "bidirectional"))
      (node (ref "J5") (pin "4") (pinfunction "4_4") (pintype "bidirectional"))
      (node (ref "J5") (pin "5") (pinfunction "5_5") (pintype "bidirectional"))
      (node (ref "J5") (pin "6") (pinfunction "6_6") (pintype "bidirectional"))
      (node (ref "J5") (pin "7") (pinfunction "7_7") (pintype "bidirectional"))
      (node (ref "J5") (pin "8") (pinfunction "8_8") (pintype "bidirectional"))
      (node (ref "J5") (pin "9") (pinfunction "9_9") (pintype "bidirectional"))
      (node (ref "J6") (pin "1") (pinfunction "1_1") (pintype "bidirectional"))
      (node (ref "J6") (pin "10") (pinfunction "10_10") (pintype "bidirectional"))
      (node (ref "J6") (pin "2") (pinfunction "2_2") (pintype "bidirectional"))
      (node (ref "J6") (pin "3") (pinfunction "3_3") (pintype "bidirectional"))
      (node (ref "J6") (pin "4") (pinfunction "4_4") (pintype "bidirectional"))
      (node (ref "J6") (pin "5") (pinfunction "5_5") (pintype "bidirectional"))
      (node (ref "J6") (pin "6") (pinfunction "6_6") (pintype "bidirectional"))
      (node (ref "J6") (pin "7") (pinfunction "7_7") (pintype "bidirectional"))
      (node (ref "J6") (pin "8") (pinfunction "8_8") (pintype "bidirectional"))
      (node (ref "J6") (pin "9") (pinfunction "9_9") (pintype "bidirectional"))
      (node (ref "R10") (pin "1") (pinfunction "1_1") (pintype "passive"))
      (node (ref "X4") (pin "1") (pinfunction "1_1") (pintype "passive"))
    )
    (net (code "4") (name "BOOT0") (class "Default")
      (node (ref "IC2") (pin "60") (pinfunction "BOOT0_60") (pintype "bidirectional"))
      (node (ref "R1") (pin "1") (pinfunction "1_1") (pintype "passive"))
    )
    (net (code "5") (name "CANH") (class "Default")
      (node (ref "IC1") (pin "7") (pinfunction "CANH_7") (pintype "bidirectional"))
      (node (ref "J2") (pin "2") (pinfunction "2_2") (pintype "bidirectional"))
      (node (ref "J2") (pin "6") (pinfunction "6_6") (pintype "bidirectional"))
      (node (ref "R9") (pin "2") (pinfunction "2_2") (pintype "passive"))
    )
    (net (code "6") (name "CANL") (class "Default")
      (node (ref "IC1") (pin "6") (pinfunction "CANL_6") (pintype "bidirectional"))
      (node (ref "J2") (pin "3") (pinfunction "3_3") (pintype "bidirectional"))
      (node (ref "J2") (pin "7") (pinfunction "7_7") (pintype "bidirectional"))
      (node (ref "R9") (pin "1") (pinfunction "1_1") (pintype "passive"))
    )
    (net (code "7") (name "CAN_RX") (class "Default")
      (node (ref "IC1") (pin "4") (pinfunction "RXD_4") (pintype "bidirectional"))
      (node (ref "IC2") (pin "44") (pinfunction "PA11_44") (pintype "bidirectional"))
    )
    (net (code "8") (name "CAN_TX") (class "Default")
      (node (ref "IC1") (pin "1") (pinfunction "TXD_1") (pintype "bidirectional"))
      (node (ref "IC2") (pin "45") (pinfunction "PA12_45") (pintype "bidirectional"))
    )
    (net (code "9") (name "ENCODER1-A") (class "Default")
      (node (ref "IC2") (pin "58") (pinfunction "PB6_58") (pintype "bidirectional"))
      (node (ref "R47") (pin "1") (pinfunction "1_1") (pintype "passive"))
      (node (ref "X1") (pin "5") (pinfunction "5_5") (pintype "passive"))
    )
    (net (code "10") (name "ENCODER1-B") (class "Default")
      (node (ref "IC2") (pin "59") (pinfunction "PB7_59") (pintype "bidirectional"))
      (node (ref "R55") (pin "1") (pinfunction "1_1") (pintype "passive"))
      (node (ref "X1") (pin "3") (pinfunction "3_3") (pintype "passive"))
    )
    (net (code "11") (name "ENCODER2-A") (class "Default")
      (node (ref "IC2") (pin "56") (pinfunction "PB4_56") (pintype "bidirectional"))
      (node (ref "R49") (pin "1") (pinfunction "1_1") (pintype "passive"))
      (node (ref "X2") (pin "5") (pinfunction "5_5") (pintype "passive"))
    )
    (net (code "12") (name "ENCODER2-B") (class "Default")
      (node (ref "IC2") (pin "57") (pinfunction "PB5_57") (pintype "bidirectional"))
      (node (ref "R57") (pin "1") (pinfunction "1_1") (pintype "passive"))
      (node (ref "X2") (pin "3") (pinfunction "3_3") (pintype "passive"))
    )
    (net (code "13") (name "ENCODER3-A") (class "Default")
      (node (ref "IC2") (pin "50") (pinfunction "PA15_50") (pintype "bidirectional"))
      (node (ref "R5") (pin "1") (pinfunction "1_1") (pintype "passive"))
      (node (ref "X6") (pin "5") (pinfunction "5_5") (pintype "passive"))
    )
    (net (code "14") (name "ENCODER3-B") (class "Default")
      (node (ref "IC2") (pin "55") (pinfunction "PB3_55") (pintype "bidirectional"))
      (node (ref "R51") (pin "1") (pinfunction "1_1") (pintype "passive"))
      (node (ref "X6") (pin "3") (pinfunction "3_3") (pintype "passive"))
    )
    (net (code "15") (name "ENCODER4-A") (class "Default")
      (node (ref "IC2") (pin "41") (pinfunction "PA8_41") (pintype "bidirectional"))
      (node (ref "R53") (pin "1") (pinfunction "1_1") (pintype "passive"))
      (node (ref "X5") (pin "5") (pinfunction "5_5") (pintype "passive"))
    )
    (net (code "16") (name "ENCODER4-B") (class "Default")
      (node (ref "IC2") (pin "42") (pinfunction "PA9_42") (pintype "bidirectional"))
      (node (ref "R61") (pin "1") (pinfunction "1_1") (pintype "passive"))
      (node (ref "X5") (pin "3") (pinfunction "3_3") (pintype "passive"))
    )
    (net (code "17") (name "GND") (class "Default")
      (node (ref "100U") (pin "2") (pinfunction "2_2") (pintype "passive"))
      (node (ref "C10") (pin "1") (pinfunction "1_1") (pintype "bidirectional"))
      (node (ref "C11") (pin "1") (pinfunction "1_1") (pintype "bidirectional"))
      (node (ref "C12") (pin "1") (pinfunction "1_1") (pintype "bidirectional"))
      (node (ref "C13") (pin "1") (pinfunction "1_1") (pintype "bidirectional"))
      (node (ref "C14") (pin "1") (pinfunction "1_1") (pintype "bidirectional"))
      (node (ref "C15") (pin "1") (pinfunction "1_1") (pintype "bidirectional"))
      (node (ref "C16") (pin "1") (pinfunction "1_1") (pintype "bidirectional"))
      (node (ref "C17") (pin "1") (pinfunction "1_1") (pintype "bidirectional"))
      (node (ref "C18") (pin "1") (pinfunction "1_1") (pintype "bidirectional"))
      (node (ref "C19") (pin "1") (pinfunction "1_1") (pintype "bidirectional"))
      (node (ref "C20") (pin "1") (pinfunction "1_1") (pintype "bidirectional"))
      (node (ref "C21") (pin "1") (pinfunction "1_1") (pintype "bidirectional"))
      (node (ref "C23") (pin "1") (pinfunction "1_1") (pintype "bidirectional"))
      (node (ref "C25") (pin "2") (pinfunction "2_2") (pintype "passive"))
      (node (ref "C27") (pin "1") (pinfunction "1_1") (pintype "bidirectional"))
      (node (ref "C28") (pin "1") (pinfunction "1_1") (pintype "bidirectional"))
      (node (ref "C29") (pin "1") (pinfunction "1_1") (pintype "bidirectional"))
      (node (ref "C5") (pin "1") (pinfunction "1_1") (pintype "bidirectional"))
      (node (ref "C6") (pin "1") (pinfunction "1_1") (pintype "bidirectional"))
      (node (ref "C7") (pin "1") (pinfunction "1_1") (pintype "bidirectional"))
      (node (ref "C8") (pin "1") (pinfunction "1_1") (pintype "bidirectional"))
      (node (ref "C9") (pin "1") (pinfunction "1_1") (pintype "bidirectional"))
      (node (ref "IC1") (pin "2") (pinfunction "GND_2") (pintype "bidirectional"))
      (node (ref "IC1") (pin "8") (pinfunction "S_8") (pintype "bidirectional"))
      (node (ref "IC2") (pin "12") (pinfunction "VSSA_12") (pintype "power_in"))
      (node (ref "IC2") (pin "18") (pinfunction "VSS_1_18") (pintype "power_in"))
      (node (ref "IC2") (pin "31") (pinfunction "VSS_2_31") (pintype "power_in"))
      (node (ref "IC2") (pin "47") (pinfunction "VSS_3_47") (pintype "power_in"))
      (node (ref "IC2") (pin "63") (pinfunction "VSS_4_63") (pintype "power_in"))
      (node (ref "J2") (pin "4") (pinfunction "4_4") (pintype "bidirectional"))
      (node (ref "J2") (pin "8") (pinfunction "8_8") (pintype "bidirectional"))
      (node (ref "Q10") (pin "3") (pinfunction "C_3") (pintype "bidirectional"))
      (node (ref "Q12") (pin "3") (pinfunction "C_3") (pintype "bidirectional"))
      (node (ref "Q2") (pin "3") (pinfunction "C_3") (pintype "bidirectional"))
      (node (ref "Q3") (pin "3") (pinfunction "C_3") (pintype "bidirectional"))
      (node (ref "Q4") (pin "3") (pinfunction "C_3") (pintype "bidirectional"))
      (node (ref "Q5") (pin "3") (pinfunction "C_3") (pintype "bidirectional"))
      (node (ref "Q6") (pin "3") (pinfunction "C_3") (pintype "bidirectional"))
      (node (ref "Q7") (pin "3") (pinfunction "C_3") (pintype "bidirectional"))
      (node (ref "Q8") (pin "3") (pinfunction "C_3") (pintype "bidirectional"))
      (node (ref "Q9") (pin "3") (pinfunction "C_3") (pintype "bidirectional"))
      (node (ref "R1") (pin "2") (pinfunction "2_2") (pintype "passive"))
      (node (ref "R2") (pin "2") (pinfunction "2_2") (pintype "passive"))
      (node (ref "R3") (pin "2") (pinfunction "2_2") (pintype "passive"))
      (node (ref "R4") (pin "1") (pinfunction "1_1") (pintype "passive"))
      (node (ref "S2") (pin "C1") (pinfunction "COM_1_C1") (pintype "bidirectional"))
      (node (ref "S2") (pin "D1") (pinfunction "COM_2_D1") (pintype "bidirectional"))
      (node (ref "SL1") (pin "3") (pinfunction "3_3") (pintype "passive"))
      (node (ref "TR1") (pin "2") (pinfunction "S_2") (pintype "bidirectional"))
      (node (ref "TR10") (pin "2") (pinfunction "S_2") (pintype "bidirectional"))
      (node (ref "TR11") (pin "2") (pinfunction "S_2") (pintype "bidirectional"))
      (node (ref "TR12") (pin "2") (pinfunction "S_2") (pintype "bidirectional"))
      (node (ref "TR13") (pin "2") (pinfunction "S_2") (pintype "bidirectional"))
      (node (ref "TR14") (pin "2") (pinfunction "S_2") (pintype "bidirectional"))
      (node (ref "TR15") (pin "2") (pinfunction "S_2") (pintype "bidirectional"))
      (node (ref "TR16") (pin "2") (pinfunction "S_2") (pintype "bidirectional"))
      (node (ref "TR17") (pin "2") (pinfunction "S_2") (pintype "bidirectional"))
      (node (ref "TR18") (pin "2") (pinfunction "S_2") (pintype "bidirectional"))
      (node (ref "TR19") (pin "2") (pinfunction "S_2") (pintype "bidirectional"))
      (node (ref "TR2") (pin "2") (pinfunction "S_2") (pintype "bidirectional"))
      (node (ref "TR20") (pin "2") (pinfunction "S_2") (pintype "bidirectional"))
      (node (ref "TR21") (pin "2") (pinfunction "S_2") (pintype "bidirectional"))
      (node (ref "TR22") (pin "2") (pinfunction "S_2") (pintype "bidirectional"))
      (node (ref "TR3") (pin "2") (pinfunction "S_2") (pintype "bidirectional"))
      (node (ref "TR4") (pin "2") (pinfunction "S_2") (pintype "bidirectional"))
      (node (ref "TR5") (pin "2") (pinfunction "S_2") (pintype "bidirectional"))
      (node (ref "TR6") (pin "2") (pinfunction "S_2") (pintype "bidirectional"))
      (node (ref "TR7") (pin "2") (pinfunction "S_2") (pintype "bidirectional"))
      (node (ref "TR8") (pin "2") (pinfunction "S_2") (pintype "bidirectional"))
      (node (ref "TR9") (pin "2") (pinfunction "S_2") (pintype "bidirectional"))
      (node (ref "U1") (pin "1") (pinfunction "GND_1") (pintype "passive"))
      (node (ref "X1") (pin "1") (pinfunction "1_1") (pintype "passive"))
      (node (ref "X2") (pin "1") (pinfunction "1_1") (pintype "passive"))
      (node (ref "X3") (pin "3") (pinfunction "3_3") (pintype "passive"))
      (node (ref "X5") (pin "1") (pinfunction "1_1") (pintype "passive"))
      (node (ref "X6") (pin "1") (pinfunction "1_1") (pintype "passive"))
      (node (ref "X9") (pin "2") (pinfunction "2_2") (pintype "passive"))
    )
    (net (code "18") (name "GND-M") (class "Default")
      (node (ref "C1") (pin "2") (pinfunction "-_2") (pintype "bidirectional"))
      (node (ref "C2") (pin "2") (pinfunction "-_2") (pintype "bidirectional"))
      (node (ref "C3") (pin "2") (pinfunction "-_2") (pintype "bidirectional"))
      (node (ref "C4") (pin "2") (pinfunction "-_2") (pintype "bidirectional"))
      (node (ref "J1") (pin "11") (pinfunction "11_11") (pintype "bidirectional"))
      (node (ref "J1") (pin "12") (pinfunction "12_12") (pintype "bidirectional"))
      (node (ref "J1") (pin "13") (pinfunction "13_13") (pintype "bidirectional"))
      (node (ref "J1") (pin "14") (pinfunction "14_14") (pintype "bidirectional"))
      (node (ref "J1") (pin "15") (pinfunction "15_15") (pintype "bidirectional"))
      (node (ref "J1") (pin "16") (pinfunction "16_16") (pintype "bidirectional"))
      (node (ref "J1") (pin "17") (pinfunction "17_17") (pintype "bidirectional"))
      (node (ref "J1") (pin "18") (pinfunction "18_18") (pintype "bidirectional"))
      (node (ref "J1") (pin "19") (pinfunction "19_19") (pintype "bidirectional"))
      (node (ref "J1") (pin "20") (pinfunction "20_20") (pintype "bidirectional"))
      (node (ref "J3") (pin "11") (pinfunction "11_11") (pintype "bidirectional"))
      (node (ref "J3") (pin "12") (pinfunction "12_12") (pintype "bidirectional"))
      (node (ref "J3") (pin "13") (pinfunction "13_13") (pintype "bidirectional"))
      (node (ref "J3") (pin "14") (pinfunction "14_14") (pintype "bidirectional"))
      (node (ref "J3") (pin "15") (pinfunction "15_15") (pintype "bidirectional"))
      (node (ref "J3") (pin "16") (pinfunction "16_16") (pintype "bidirectional"))
      (node (ref "J3") (pin "17") (pinfunction "17_17") (pintype "bidirectional"))
      (node (ref "J3") (pin "18") (pinfunction "18_18") (pintype "bidirectional"))
      (node (ref "J3") (pin "19") (pinfunction "19_19") (pintype "bidirectional"))
      (node (ref "J3") (pin "20") (pinfunction "20_20") (pintype "bidirectional"))
      (node (ref "J4") (pin "11") (pinfunction "11_11") (pintype "bidirectional"))
      (node (ref "J4") (pin "12") (pinfunction "12_12") (pintype "bidirectional"))
      (node (ref "J4") (pin "13") (pinfunction "13_13") (pintype "bidirectional"))
      (node (ref "J4") (pin "14") (pinfunction "14_14") (pintype "bidirectional"))
      (node (ref "J4") (pin "15") (pinfunction "15_15") (pintype "bidirectional"))
      (node (ref "J4") (pin "16") (pinfunction "16_16") (pintype "bidirectional"))
      (node (ref "J4") (pin "17") (pinfunction "17_17") (pintype "bidirectional"))
      (node (ref "J4") (pin "18") (pinfunction "18_18") (pintype "bidirectional"))
      (node (ref "J4") (pin "19") (pinfunction "19_19") (pintype "bidirectional"))
      (node (ref "J4") (pin "20") (pinfunction "20_20") (pintype "bidirectional"))
      (node (ref "J5") (pin "11") (pinfunction "11_11") (pintype "bidirectional"))
      (node (ref "J5") (pin "12") (pinfunction "12_12") (pintype "bidirectional"))
      (node (ref "J5") (pin "13") (pinfunction "13_13") (pintype "bidirectional"))
      (node (ref "J5") (pin "14") (pinfunction "14_14") (pintype "bidirectional"))
      (node (ref "J5") (pin "15") (pinfunction "15_15") (pintype "bidirectional"))
      (node (ref "J5") (pin "16") (pinfunction "16_16") (pintype "bidirectional"))
      (node (ref "J5") (pin "17") (pinfunction "17_17") (pintype "bidirectional"))
      (node (ref "J5") (pin "18") (pinfunction "18_18") (pintype "bidirectional"))
      (node (ref "J5") (pin "19") (pinfunction "19_19") (pintype "bidirectional"))
      (node (ref "J5") (pin "20") (pinfunction "20_20") (pintype "bidirectional"))
      (node (ref "J6") (pin "11") (pinfunction "11_11") (pintype "bidirectional"))
      (node (ref "J6") (pin "12") (pinfunction "12_12") (pintype "bidirectional"))
      (node (ref "J6") (pin "13") (pinfunction "13_13") (pintype "bidirectional"))
      (node (ref "J6") (pin "14") (pinfunction "14_14") (pintype "bidirectional"))
      (node (ref "J6") (pin "15") (pinfunction "15_15") (pintype "bidirectional"))
      (node (ref "J6") (pin "16") (pinfunction "16_16") (pintype "bidirectional"))
      (node (ref "J6") (pin "17") (pinfunction "17_17") (pintype "bidirectional"))
      (node (ref "J6") (pin "18") (pinfunction "18_18") (pintype "bidirectional"))
      (node (ref "J6") (pin "19") (pinfunction "19_19") (pintype "bidirectional"))
      (node (ref "J6") (pin "20") (pinfunction "20_20") (pintype "bidirectional"))
      (node (ref "LED1") (pin "K") (pinfunction "K_K") (pintype "passive"))
      (node (ref "X4") (pin "2") (pinfunction "2_2") (pintype "passive"))
    )
    (net (code "19") (name "I2C_SCL") (class "Default")
      (node (ref "IC2") (pin "61") (pinfunction "PB8_61") (pintype "bidirectional"))
      (node (ref "JP3") (pin "2") (pinfunction "2_2") (pintype "passive"))
    )
    (net (code "20") (name "I2C_SDA") (class "Default")
      (node (ref "IC2") (pin "62") (pinfunction "PB9_62") (pintype "bidirectional"))
      (node (ref "JP3") (pin "1") (pinfunction "1_1") (pintype "passive"))
    )
    (net (code "21") (name "MD1-A") (class "Default")
      (node (ref "IC2") (pin "39") (pinfunction "PC8_39") (pintype "bidirectional"))
      (node (ref "R18") (pin "1") (pinfunction "1_1") (pintype "passive"))
      (node (ref "R19") (pin "1") (pinfunction "1_1") (pintype "passive"))
    )
    (net (code "22") (name "MD1-B") (class "Default")
      (node (ref "IC2") (pin "40") (pinfunction "PC9_40") (pintype "bidirectional"))
      (node (ref "R33") (pin "1") (pinfunction "1_1") (pintype "passive"))
      (node (ref "R34") (pin "1") (pinfunction "1_1") (pintype "passive"))
    )
    (net (code "23") (name "MD2-A") (class "Default")
      (node (ref "IC2") (pin "37") (pinfunction "PC6_37") (pintype "bidirectional"))
      (node (ref "R21") (pin "1") (pinfunction "1_1") (pintype "passive"))
      (node (ref "R22") (pin "1") (pinfunction "1_1") (pintype "passive"))
    )
    (net (code "24") (name "MD2-B") (class "Default")
      (node (ref "IC2") (pin "38") (pinfunction "PC7_38") (pintype "bidirectional"))
      (node (ref "R36") (pin "1") (pinfunction "1_1") (pintype "passive"))
      (node (ref "R37") (pin "1") (pinfunction "1_1") (pintype "passive"))
    )
    (net (code "25") (name "MD3-A") (class "Default")
      (node (ref "IC2") (pin "35") (pinfunction "PB14_35") (pintype "bidirectional"))
      (node (ref "R24") (pin "1") (pinfunction "1_1") (pintype "passive"))
      (node (ref "R25") (pin "1") (pinfunction "1_1") (pintype "passive"))
    )
    (net (code "26") (name "MD3-B") (class "Default")
      (node (ref "IC2") (pin "36") (pinfunction "PB15_36") (pintype "bidirectional"))
      (node (ref "R39") (pin "1") (pinfunction "1_1") (pintype "passive"))
      (node (ref "R40") (pin "1") (pinfunction "1_1") (pintype "passive"))
    )
    (net (code "27") (name "MD4-A") (class "Default")
      (node (ref "IC2") (pin "16") (pinfunction "PA2_16") (pintype "bidirectional"))
      (node (ref "R27") (pin "1") (pinfunction "1_1") (pintype "passive"))
      (node (ref "R28") (pin "1") (pinfunction "1_1") (pintype "passive"))
    )
    (net (code "28") (name "MD4-B") (class "Default")
      (node (ref "IC2") (pin "17") (pinfunction "PA3_17") (pintype "bidirectional"))
      (node (ref "R42") (pin "1") (pinfunction "1_1") (pintype "passive"))
      (node (ref "R43") (pin "1") (pinfunction "1_1") (pintype "passive"))
    )
    (net (code "29") (name "MD5-A") (class "Default")
      (node (ref "IC2") (pin "14") (pinfunction "PA0-WKUP_14") (pintype "bidirectional"))
      (node (ref "R30") (pin "1") (pinfunction "1_1") (pintype "passive"))
      (node (ref "R31") (pin "1") (pinfunction "1_1") (pintype "passive"))
    )
    (net (code "30") (name "MD5-B") (class "Default")
      (node (ref "IC2") (pin "15") (pinfunction "PA1_15") (pintype "bidirectional"))
      (node (ref "R45") (pin "1") (pinfunction "1_1") (pintype "passive"))
      (node (ref "R46") (pin "1") (pinfunction "1_1") (pintype "passive"))
    )
    (net (code "31") (name "NRST") (class "Default")
      (node (ref "C23") (pin "2") (pinfunction "2_2") (pintype "bidirectional"))
      (node (ref "IC2") (pin "7") (pinfunction "NRST_7") (pintype "bidirectional"))
      (node (ref "S2") (pin "A1") (pinfunction "NO_1_A1") (pintype "bidirectional"))
      (node (ref "SL1") (pin "5") (pinfunction "5_5") (pintype "passive"))
      (node (ref "X9") (pin "1") (pinfunction "1_1") (pintype "passive"))
    )
    (net (code "32") (name "Net-(LED1-PadA)") (class "Default")
      (node (ref "LED1") (pin "A") (pinfunction "A_A") (pintype "passive"))
      (node (ref "R10") (pin "2") (pinfunction "2_2") (pintype "passive"))
    )
    (net (code "33") (name "Net-(LED2-PadK)") (class "Default")
      (node (ref "LED2") (pin "K") (pinfunction "K_K") (pintype "passive"))
      (node (ref "R2") (pin "1") (pinfunction "1_1") (pintype "passive"))
    )
    (net (code "34") (name "Net-(LED3-PadK)") (class "Default")
      (node (ref "LED3") (pin "K") (pinfunction "K_K") (pintype "passive"))
      (node (ref "R3") (pin "1") (pinfunction "1_1") (pintype "passive"))
    )
    (net (code "35") (name "Net-(LED4-PadK)") (class "Default")
      (node (ref "LED4") (pin "K") (pinfunction "K_K") (pintype "passive"))
      (node (ref "R4") (pin "2") (pinfunction "2_2") (pintype "passive"))
    )
    (net (code "36") (name "Net-(LED5-PadA)") (class "Default")
      (node (ref "LED5") (pin "A") (pinfunction "A_A") (pintype "passive"))
      (node (ref "R6") (pin "2") (pinfunction "2_2") (pintype "passive"))
    )
    (net (code "37") (name "Net-(LED6-PadK)") (class "Default")
      (node (ref "LED6") (pin "K") (pinfunction "K_K") (pintype "passive"))
      (node (ref "R7") (pin "2") (pinfunction "2_2") (pintype "passive"))
    )
    (net (code "38") (name "Net-(LED7-PadK)") (class "Default")
      (node (ref "LED7") (pin "K") (pinfunction "K_K") (pintype "passive"))
      (node (ref "R8") (pin "2") (pinfunction "2_2") (pintype "passive"))
    )
    (net (code "39") (name "Net-(LED8-PadK)") (class "Default")
      (node (ref "LED8") (pin "K") (pinfunction "K_K") (pintype "passive"))
      (node (ref "R12") (pin "2") (pinfunction "2_2") (pintype "passive"))
    )
    (net (code "40") (name "Net-(LED9-PadK)") (class "Default")
      (node (ref "LED9") (pin "K") (pinfunction "K_K") (pintype "passive"))
      (node (ref "R15") (pin "2") (pinfunction "2_2") (pintype "passive"))
    )
    (net (code "41") (name "Net-(LED10-PadK)") (class "Default")
      (node (ref "LED10") (pin "K") (pinfunction "K_K") (pintype "passive"))
      (node (ref "R17") (pin "2") (pinfunction "2_2") (pintype "passive"))
    )
    (net (code "42") (name "Net-(LED11-PadK)") (class "Default")
      (node (ref "LED11") (pin "K") (pinfunction "K_K") (pintype "passive"))
      (node (ref "R20") (pin "2") (pinfunction "2_2") (pintype "passive"))
    )
    (net (code "43") (name "Net-(LED12-PadK)") (class "Default")
      (node (ref "LED12") (pin "K") (pinfunction "K_K") (pintype "passive"))
      (node (ref "R23") (pin "2") (pinfunction "2_2") (pintype "passive"))
    )
    (net (code "44") (name "Net-(LED13-PadK)") (class "Default")
      (node (ref "LED13") (pin "K") (pinfunction "K_K") (pintype "passive"))
      (node (ref "R26") (pin "2") (pinfunction "2_2") (pintype "passive"))
    )
    (net (code "45") (name "Net-(LED14-PadK)") (class "Default")
      (node (ref "LED14") (pin "K") (pinfunction "K_K") (pintype "passive"))
      (node (ref "R29") (pin "2") (pinfunction "2_2") (pintype "passive"))
    )
    (net (code "46") (name "Net-(LED15-PadK)") (class "Default")
      (node (ref "LED15") (pin "K") (pinfunction "K_K") (pintype "passive"))
      (node (ref "R32") (pin "2") (pinfunction "2_2") (pintype "passive"))
    )
    (net (code "47") (name "Net-(LED16-PadK)") (class "Default")
      (node (ref "LED16") (pin "K") (pinfunction "K_K") (pintype "passive"))
      (node (ref "R35") (pin "2") (pinfunction "2_2") (pintype "passive"))
    )
    (net (code "48") (name "Net-(LED17-PadK)") (class "Default")
      (node (ref "LED17") (pin "K") (pinfunction "K_K") (pintype "passive"))
      (node (ref "R38") (pin "2") (pinfunction "2_2") (pintype "passive"))
    )
    (net (code "49") (name "Net-(LED18-PadK)") (class "Default")
      (node (ref "LED18") (pin "K") (pinfunction "K_K") (pintype "passive"))
      (node (ref "R41") (pin "2") (pinfunction "2_2") (pintype "passive"))
    )
    (net (code "50") (name "Net-(LED19-PadK)") (class "Default")
      (node (ref "LED19") (pin "K") (pinfunction "K_K") (pintype "passive"))
      (node (ref "R44") (pin "2") (pinfunction "2_2") (pintype "passive"))
    )
    (net (code "51") (name "Net-(LED20-PadA)") (class "Default")
      (node (ref "LED20") (pin "A") (pinfunction "A_A") (pintype "passive"))
      (node (ref "R48") (pin "2") (pinfunction "2_2") (pintype "passive"))
    )
    (net (code "52") (name "Net-(LED21-PadA)") (class "Default")
      (node (ref "LED21") (pin "A") (pinfunction "A_A") (pintype "passive"))
      (node (ref "R50") (pin "2") (pinfunction "2_2") (pintype "passive"))
    )
    (net (code "53") (name "Net-(LED22-PadA)") (class "Default")
      (node (ref "LED22") (pin "A") (pinfunction "A_A") (pintype "passive"))
      (node (ref "R52") (pin "2") (pinfunction "2_2") (pintype "passive"))
    )
    (net (code "54") (name "Net-(LED23-PadA)") (class "Default")
      (node (ref "LED23") (pin "A") (pinfunction "A_A") (pintype "passive"))
      (node (ref "R54") (pin "2") (pinfunction "2_2") (pintype "passive"))
    )
    (net (code "55") (name "Net-(LED24-PadA)") (class "Default")
      (node (ref "LED24") (pin "A") (pinfunction "A_A") (pintype "passive"))
      (node (ref "R62") (pin "2") (pinfunction "2_2") (pintype "passive"))
    )
    (net (code "56") (name "Net-(LED26-PadA)") (class "Default")
      (node (ref "LED26") (pin "A") (pinfunction "A_A") (pintype "passive"))
      (node (ref "R58") (pin "2") (pinfunction "2_2") (pintype "passive"))
    )
    (net (code "57") (name "Net-(LED27-PadA)") (class "Default")
      (node (ref "LED27") (pin "A") (pinfunction "A_A") (pintype "passive"))
      (node (ref "R56") (pin "2") (pinfunction "2_2") (pintype "passive"))
    )
    (net (code "58") (name "Net-(Q2-B)") (class "Default")
      (node (ref "Q2") (pin "1") (pinfunction "B_1") (pintype "bidirectional"))
      (node (ref "R22") (pin "2") (pinfunction "2_2") (pintype "passive"))
    )
    (net (code "59") (name "Net-(Q3-B)") (class "Default")
      (node (ref "Q3") (pin "1") (pinfunction "B_1") (pintype "bidirectional"))
      (node (ref "R25") (pin "2") (pinfunction "2_2") (pintype "passive"))
    )
    (net (code "60") (name "Net-(Q4-B)") (class "Default")
      (node (ref "Q4") (pin "1") (pinfunction "B_1") (pintype "bidirectional"))
      (node (ref "R28") (pin "2") (pinfunction "2_2") (pintype "passive"))
    )
    (net (code "61") (name "Net-(Q5-B)") (class "Default")
      (node (ref "Q5") (pin "1") (pinfunction "B_1") (pintype "bidirectional"))
      (node (ref "R31") (pin "2") (pinfunction "2_2") (pintype "passive"))
    )
    (net (code "62") (name "Net-(Q6-B)") (class "Default")
      (node (ref "Q6") (pin "1") (pinfunction "B_1") (pintype "bidirectional"))
      (node (ref "R34") (pin "2") (pinfunction "2_2") (pintype "passive"))
    )
    (net (code "63") (name "Net-(Q7-B)") (class "Default")
      (node (ref "Q7") (pin "1") (pinfunction "B_1") (pintype "bidirectional"))
      (node (ref "R37") (pin "2") (pinfunction "2_2") (pintype "passive"))
    )
    (net (code "64") (name "Net-(Q8-B)") (class "Default")
      (node (ref "Q8") (pin "1") (pinfunction "B_1") (pintype "bidirectional"))
      (node (ref "R40") (pin "2") (pinfunction "2_2") (pintype "passive"))
    )
    (net (code "65") (name "Net-(Q9-B)") (class "Default")
      (node (ref "Q9") (pin "1") (pinfunction "B_1") (pintype "bidirectional"))
      (node (ref "R43") (pin "2") (pinfunction "2_2") (pintype "passive"))
    )
    (net (code "66") (name "Net-(Q10-B)") (class "Default")
      (node (ref "Q10") (pin "1") (pinfunction "B_1") (pintype "bidirectional"))
      (node (ref "R46") (pin "2") (pinfunction "2_2") (pintype "passive"))
    )
    (net (code "67") (name "Net-(Q12-B)") (class "Default")
      (node (ref "Q12") (pin "1") (pinfunction "B_1") (pintype "bidirectional"))
      (node (ref "R19") (pin "2") (pinfunction "2_2") (pintype "passive"))
    )
    (net (code "68") (name "Net-(TR1-D)") (class "Default")
      (node (ref "R8") (pin "1") (pinfunction "1_1") (pintype "passive"))
      (node (ref "TR1") (pin "3") (pinfunction "D_3") (pintype "bidirectional"))
    )
    (net (code "69") (name "Net-(TR1-G)") (class "Default")
      (node (ref "R11") (pin "2") (pinfunction "2_2") (pintype "passive"))
      (node (ref "TR1") (pin "1") (pinfunction "G_1") (pintype "bidirectional"))
    )
    (net (code "70") (name "Net-(TR2-D)") (class "Default")
      (node (ref "R7") (pin "1") (pinfunction "1_1") (pintype "passive"))
      (node (ref "TR2") (pin "3") (pinfunction "D_3") (pintype "bidirectional"))
    )
    (net (code "71") (name "Net-(TR2-G)") (class "Default")
      (node (ref "R14") (pin "2") (pinfunction "2_2") (pintype "passive"))
      (node (ref "TR2") (pin "1") (pinfunction "G_1") (pintype "bidirectional"))
    )
    (net (code "72") (name "Net-(TR3-D)") (class "Default")
      (node (ref "R12") (pin "1") (pinfunction "1_1") (pintype "passive"))
      (node (ref "TR3") (pin "3") (pinfunction "D_3") (pintype "bidirectional"))
    )
    (net (code "73") (name "Net-(TR3-G)") (class "Default")
      (node (ref "R13") (pin "2") (pinfunction "2_2") (pintype "passive"))
      (node (ref "TR3") (pin "1") (pinfunction "G_1") (pintype "bidirectional"))
    )
    (net (code "74") (name "Net-(TR4-D)") (class "Default")
      (node (ref "R15") (pin "1") (pinfunction "1_1") (pintype "passive"))
      (node (ref "TR4") (pin "3") (pinfunction "D_3") (pintype "bidirectional"))
    )
    (net (code "75") (name "Net-(TR4-G)") (class "Default")
      (node (ref "R16") (pin "2") (pinfunction "2_2") (pintype "passive"))
      (node (ref "TR4") (pin "1") (pinfunction "G_1") (pintype "bidirectional"))
    )
    (net (code "76") (name "Net-(TR5-D)") (class "Default")
      (node (ref "R17") (pin "1") (pinfunction "1_1") (pintype "passive"))
      (node (ref "TR5") (pin "3") (pinfunction "D_3") (pintype "bidirectional"))
    )
    (net (code "77") (name "Net-(TR5-G)") (class "Default")
      (node (ref "R18") (pin "2") (pinfunction "2_2") (pintype "passive"))
      (node (ref "TR5") (pin "1") (pinfunction "G_1") (pintype "bidirectional"))
    )
    (net (code "78") (name "Net-(TR6-D)") (class "Default")
      (node (ref "R20") (pin "1") (pinfunction "1_1") (pintype "passive"))
      (node (ref "TR6") (pin "3") (pinfunction "D_3") (pintype "bidirectional"))
    )
    (net (code "79") (name "Net-(TR6-G)") (class "Default")
      (node (ref "R21") (pin "2") (pinfunction "2_2") (pintype "passive"))
      (node (ref "TR6") (pin "1") (pinfunction "G_1") (pintype "bidirectional"))
    )
    (net (code "80") (name "Net-(TR7-D)") (class "Default")
      (node (ref "R23") (pin "1") (pinfunction "1_1") (pintype "passive"))
      (node (ref "TR7") (pin "3") (pinfunction "D_3") (pintype "bidirectional"))
    )
    (net (code "81") (name "Net-(TR7-G)") (class "Default")
      (node (ref "R24") (pin "2") (pinfunction "2_2") (pintype "passive"))
      (node (ref "TR7") (pin "1") (pinfunction "G_1") (pintype "bidirectional"))
    )
    (net (code "82") (name "Net-(TR8-D)") (class "Default")
      (node (ref "R26") (pin "1") (pinfunction "1_1") (pintype "passive"))
      (node (ref "TR8") (pin "3") (pinfunction "D_3") (pintype "bidirectional"))
    )
    (net (code "83") (name "Net-(TR8-G)") (class "Default")
      (node (ref "R27") (pin "2") (pinfunction "2_2") (pintype "passive"))
      (node (ref "TR8") (pin "1") (pinfunction "G_1") (pintype "bidirectional"))
    )
    (net (code "84") (name "Net-(TR9-D)") (class "Default")
      (node (ref "R29") (pin "1") (pinfunction "1_1") (pintype "passive"))
      (node (ref "TR9") (pin "3") (pinfunction "D_3") (pintype "bidirectional"))
    )
    (net (code "85") (name "Net-(TR9-G)") (class "Default")
      (node (ref "R30") (pin "2") (pinfunction "2_2") (pintype "passive"))
      (node (ref "TR9") (pin "1") (pinfunction "G_1") (pintype "bidirectional"))
    )
    (net (code "86") (name "Net-(TR10-D)") (class "Default")
      (node (ref "R32") (pin "1") (pinfunction "1_1") (pintype "passive"))
      (node (ref "TR10") (pin "3") (pinfunction "D_3") (pintype "bidirectional"))
    )
    (net (code "87") (name "Net-(TR10-G)") (class "Default")
      (node (ref "R33") (pin "2") (pinfunction "2_2") (pintype "passive"))
      (node (ref "TR10") (pin "1") (pinfunction "G_1") (pintype "bidirectional"))
    )
    (net (code "88") (name "Net-(TR11-D)") (class "Default")
      (node (ref "R35") (pin "1") (pinfunction "1_1") (pintype "passive"))
      (node (ref "TR11") (pin "3") (pinfunction "D_3") (pintype "bidirectional"))
    )
    (net (code "89") (name "Net-(TR11-G)") (class "Default")
      (node (ref "R36") (pin "2") (pinfunction "2_2") (pintype "passive"))
      (node (ref "TR11") (pin "1") (pinfunction "G_1") (pintype "bidirectional"))
    )
    (net (code "90") (name "Net-(TR12-D)") (class "Default")
      (node (ref "R38") (pin "1") (pinfunction "1_1") (pintype "passive"))
      (node (ref "TR12") (pin "3") (pinfunction "D_3") (pintype "bidirectional"))
    )
    (net (code "91") (name "Net-(TR12-G)") (class "Default")
      (node (ref "R39") (pin "2") (pinfunction "2_2") (pintype "passive"))
      (node (ref "TR12") (pin "1") (pinfunction "G_1") (pintype "bidirectional"))
    )
    (net (code "92") (name "Net-(TR13-D)") (class "Default")
      (node (ref "R41") (pin "1") (pinfunction "1_1") (pintype "passive"))
      (node (ref "TR13") (pin "3") (pinfunction "D_3") (pintype "bidirectional"))
    )
    (net (code "93") (name "Net-(TR13-G)") (class "Default")
      (node (ref "R42") (pin "2") (pinfunction "2_2") (pintype "passive"))
      (node (ref "TR13") (pin "1") (pinfunction "G_1") (pintype "bidirectional"))
    )
    (net (code "94") (name "Net-(TR14-D)") (class "Default")
      (node (ref "R44") (pin "1") (pinfunction "1_1") (pintype "passive"))
      (node (ref "TR14") (pin "3") (pinfunction "D_3") (pintype "bidirectional"))
    )
    (net (code "95") (name "Net-(TR14-G)") (class "Default")
      (node (ref "R45") (pin "2") (pinfunction "2_2") (pintype "passive"))
      (node (ref "TR14") (pin "1") (pinfunction "G_1") (pintype "bidirectional"))
    )
    (net (code "96") (name "Net-(TR15-D)") (class "Default")
      (node (ref "LED20") (pin "K") (pinfunction "K_K") (pintype "passive"))
      (node (ref "TR15") (pin "3") (pinfunction "D_3") (pintype "bidirectional"))
    )
    (net (code "97") (name "Net-(TR15-G)") (class "Default")
      (node (ref "R47") (pin "2") (pinfunction "2_2") (pintype "passive"))
      (node (ref "TR15") (pin "1") (pinfunction "G_1") (pintype "bidirectional"))
    )
    (net (code "98") (name "Net-(TR16-D)") (class "Default")
      (node (ref "LED21") (pin "K") (pinfunction "K_K") (pintype "passive"))
      (node (ref "TR16") (pin "3") (pinfunction "D_3") (pintype "bidirectional"))
    )
    (net (code "99") (name "Net-(TR16-G)") (class "Default")
      (node (ref "R49") (pin "2") (pinfunction "2_2") (pintype "passive"))
      (node (ref "TR16") (pin "1") (pinfunction "G_1") (pintype "bidirectional"))
    )
    (net (code "100") (name "Net-(TR17-D)") (class "Default")
      (node (ref "LED27") (pin "K") (pinfunction "K_K") (pintype "passive"))
      (node (ref "TR17") (pin "3") (pinfunction "D_3") (pintype "bidirectional"))
    )
    (net (code "101") (name "Net-(TR17-G)") (class "Default")
      (node (ref "R55") (pin "2") (pinfunction "2_2") (pintype "passive"))
      (node (ref "TR17") (pin "1") (pinfunction "G_1") (pintype "bidirectional"))
    )
    (net (code "102") (name "Net-(TR18-D)") (class "Default")
      (node (ref "LED26") (pin "K") (pinfunction "K_K") (pintype "passive"))
      (node (ref "TR18") (pin "3") (pinfunction "D_3") (pintype "bidirectional"))
    )
    (net (code "103") (name "Net-(TR18-G)") (class "Default")
      (node (ref "R57") (pin "2") (pinfunction "2_2") (pintype "passive"))
      (node (ref "TR18") (pin "1") (pinfunction "G_1") (pintype "bidirectional"))
    )
    (net (code "104") (name "Net-(TR19-D)") (class "Default")
      (node (ref "LED5") (pin "K") (pinfunction "K_K") (pintype "passive"))
      (node (ref "TR19") (pin "3") (pinfunction "D_3") (pintype "bidirectional"))
    )
    (net (code "105") (name "Net-(TR19-G)") (class "Default")
      (node (ref "R5") (pin "2") (pinfunction "2_2") (pintype "passive"))
      (node (ref "TR19") (pin "1") (pinfunction "G_1") (pintype "bidirectional"))
    )
    (net (code "106") (name "Net-(TR20-D)") (class "Default")
      (node (ref "LED24") (pin "K") (pinfunction "K_K") (pintype "passive"))
      (node (ref "TR20") (pin "3") (pinfunction "D_3") (pintype "bidirectional"))
    )
    (net (code "107") (name "Net-(TR20-G)") (class "Default")
      (node (ref "R61") (pin "2") (pinfunction "2_2") (pintype "passive"))
      (node (ref "TR20") (pin "1") (pinfunction "G_1") (pintype "bidirectional"))
    )
    (net (code "108") (name "Net-(TR21-D)") (class "Default")
      (node (ref "LED23") (pin "K") (pinfunction "K_K") (pintype "passive"))
      (node (ref "TR21") (pin "3") (pinfunction "D_3") (pintype "bidirectional"))
    )
    (net (code "109") (name "Net-(TR21-G)") (class "Default")
      (node (ref "R53") (pin "2") (pinfunction "2_2") (pintype "passive"))
      (node (ref "TR21") (pin "1") (pinfunction "G_1") (pintype "bidirectional"))
    )
    (net (code "110") (name "Net-(TR22-D)") (class "Default")
      (node (ref "LED22") (pin "K") (pinfunction "K_K") (pintype "passive"))
      (node (ref "TR22") (pin "3") (pinfunction "D_3") (pintype "bidirectional"))
    )
    (net (code "111") (name "Net-(TR22-G)") (class "Default")
      (node (ref "R51") (pin "2") (pinfunction "2_2") (pintype "passive"))
      (node (ref "TR22") (pin "1") (pinfunction "G_1") (pintype "bidirectional"))
    )
    (net (code "112") (name "PA0") (class "Default")
      (node (ref "J1") (pin "23") (pinfunction "23_23") (pintype "bidirectional"))
      (node (ref "J1") (pin "24") (pinfunction "24_24") (pintype "bidirectional"))
      (node (ref "Q5") (pin "2") (pinfunction "E_2") (pintype "bidirectional"))
    )
    (net (code "113") (name "PA1") (class "Default")
      (node (ref "J1") (pin "25") (pinfunction "25_25") (pintype "bidirectional"))
      (node (ref "J1") (pin "26") (pinfunction "26_26") (pintype "bidirectional"))
      (node (ref "Q10") (pin "2") (pinfunction "E_2") (pintype "bidirectional"))
    )
    (net (code "114") (name "PA2") (class "Default")
      (node (ref "J6") (pin "23") (pinfunction "23_23") (pintype "bidirectional"))
      (node (ref "J6") (pin "24") (pinfunction "24_24") (pintype "bidirectional"))
      (node (ref "Q4") (pin "2") (pinfunction "E_2") (pintype "bidirectional"))
    )
    (net (code "115") (name "PA3") (class "Default")
      (node (ref "J6") (pin "25") (pinfunction "25_25") (pintype "bidirectional"))
      (node (ref "J6") (pin "26") (pinfunction "26_26") (pintype "bidirectional"))
      (node (ref "Q9") (pin "2") (pinfunction "E_2") (pintype "bidirectional"))
    )
    (net (code "116") (name "PB0") (class "Default")
      (node (ref "IC2") (pin "25") (pinfunction "PB0_25") (pintype "bidirectional"))
      (node (ref "JP2") (pin "3") (pinfunction "3_3") (pintype "passive"))
    )
    (net (code "117") (name "PB1") (class "Default")
      (node (ref "IC2") (pin "26") (pinfunction "PB1_26") (pintype "bidirectional"))
      (node (ref "JP2") (pin "2") (pinfunction "2_2") (pintype "passive"))
    )
    (net (code "118") (name "PB2") (class "Default")
      (node (ref "IC2") (pin "27") (pinfunction "PB2_27") (pintype "bidirectional"))
      (node (ref "JP2") (pin "1") (pinfunction "1_1") (pintype "passive"))
    )
    (net (code "119") (name "PB14") (class "Default")
      (node (ref "J5") (pin "23") (pinfunction "23_23") (pintype "bidirectional"))
      (node (ref "J5") (pin "24") (pinfunction "24_24") (pintype "bidirectional"))
      (node (ref "Q3") (pin "2") (pinfunction "E_2") (pintype "bidirectional"))
    )
    (net (code "120") (name "PB15") (class "Default")
      (node (ref "J5") (pin "25") (pinfunction "25_25") (pintype "bidirectional"))
      (node (ref "J5") (pin "26") (pinfunction "26_26") (pintype "bidirectional"))
      (node (ref "Q8") (pin "2") (pinfunction "E_2") (pintype "bidirectional"))
    )
    (net (code "121") (name "PC0") (class "Default")
      (node (ref "IC2") (pin "8") (pinfunction "PC0_8") (pintype "bidirectional"))
      (node (ref "JP1") (pin "1") (pinfunction "1_1") (pintype "passive"))
    )
    (net (code "122") (name "PC1") (class "Default")
      (node (ref "IC2") (pin "9") (pinfunction "PC1_9") (pintype "bidirectional"))
      (node (ref "JP1") (pin "2") (pinfunction "2_2") (pintype "passive"))
    )
    (net (code "123") (name "PC2") (class "Default")
      (node (ref "IC2") (pin "10") (pinfunction "PC2_10") (pintype "bidirectional"))
      (node (ref "JP1") (pin "4") (pinfunction "4_4") (pintype "passive"))
    )
    (net (code "124") (name "PC3") (class "Default")
      (node (ref "IC2") (pin "11") (pinfunction "PC3_11") (pintype "bidirectional"))
      (node (ref "JP1") (pin "6") (pinfunction "6_6") (pintype "passive"))
    )
    (net (code "125") (name "PC4") (class "Default")
      (node (ref "IC2") (pin "24") (pinfunction "PC4_24") (pintype "bidirectional"))
      (node (ref "JP2") (pin "4") (pinfunction "4_4") (pintype "passive"))
    )
    (net (code "126") (name "PC6") (class "Default")
      (node (ref "J4") (pin "23") (pinfunction "23_23") (pintype "bidirectional"))
      (node (ref "J4") (pin "24") (pinfunction "24_24") (pintype "bidirectional"))
      (node (ref "Q2") (pin "2") (pinfunction "E_2") (pintype "bidirectional"))
    )
    (net (code "127") (name "PC7") (class "Default")
      (node (ref "J4") (pin "25") (pinfunction "25_25") (pintype "bidirectional"))
      (node (ref "J4") (pin "26") (pinfunction "26_26") (pintype "bidirectional"))
      (node (ref "Q7") (pin "2") (pinfunction "E_2") (pintype "bidirectional"))
    )
    (net (code "128") (name "PC8") (class "Default")
      (node (ref "J3") (pin "25") (pinfunction "25_25") (pintype "bidirectional"))
      (node (ref "J3") (pin "26") (pinfunction "26_26") (pintype "bidirectional"))
      (node (ref "Q12") (pin "2") (pinfunction "E_2") (pintype "bidirectional"))
    )
    (net (code "129") (name "PC9") (class "Default")
      (node (ref "J3") (pin "23") (pinfunction "23_23") (pintype "bidirectional"))
      (node (ref "J3") (pin "24") (pinfunction "24_24") (pintype "bidirectional"))
      (node (ref "Q6") (pin "2") (pinfunction "E_2") (pintype "bidirectional"))
    )
    (net (code "130") (name "PC10") (class "Default")
      (node (ref "IC2") (pin "51") (pinfunction "PC10_51") (pintype "bidirectional"))
      (node (ref "R16") (pin "1") (pinfunction "1_1") (pintype "passive"))
    )
    (net (code "131") (name "PC11") (class "Default")
      (node (ref "IC2") (pin "52") (pinfunction "PC11_52") (pintype "bidirectional"))
      (node (ref "R13") (pin "1") (pinfunction "1_1") (pintype "passive"))
    )
    (net (code "132") (name "PC12") (class "Default")
      (node (ref "IC2") (pin "53") (pinfunction "PC12_53") (pintype "bidirectional"))
      (node (ref "R11") (pin "1") (pinfunction "1_1") (pintype "passive"))
    )
    (net (code "133") (name "PC13") (class "Default")
      (node (ref "IC2") (pin "2") (pinfunction "PC13_2") (pintype "bidirectional"))
      (node (ref "JP1") (pin "5") (pinfunction "5_5") (pintype "passive"))
    )
    (net (code "134") (name "PC14") (class "Default")
      (node (ref "IC2") (pin "3") (pinfunction "PC14-OSC32_IN_3") (pintype "bidirectional"))
      (node (ref "JP1") (pin "3") (pinfunction "3_3") (pintype "passive"))
    )
    (net (code "135") (name "PC15") (class "Default")
      (node (ref "C28") (pin "2") (pinfunction "2_2") (pintype "bidirectional"))
      (node (ref "IC2") (pin "4") (pinfunction "PC15-OSC32_OUT_4") (pintype "bidirectional"))
      (node (ref "LED4") (pin "A") (pinfunction "A_A") (pintype "passive"))
      (node (ref "S1") (pin "A1") (pinfunction "NO_1_A1") (pintype "bidirectional"))
    )
    (net (code "136") (name "PD2") (class "Default")
      (node (ref "IC2") (pin "54") (pinfunction "PD2_54") (pintype "bidirectional"))
      (node (ref "R14") (pin "1") (pinfunction "1_1") (pintype "passive"))
    )
    (net (code "137") (name "SPI_MISO") (class "Default")
      (node (ref "IC2") (pin "22") (pinfunction "PA6_22") (pintype "bidirectional"))
      (node (ref "X7") (pin "2") (pinfunction "2_2") (pintype "passive"))
    )
    (net (code "138") (name "SPI_MOSI") (class "Default")
      (node (ref "IC2") (pin "23") (pinfunction "PA7_23") (pintype "bidirectional"))
      (node (ref "X7") (pin "1") (pinfunction "1_1") (pintype "passive"))
    )
    (net (code "139") (name "SPI_NSS") (class "Default")
      (node (ref "IC2") (pin "20") (pinfunction "PA4_20") (pintype "bidirectional"))
      (node (ref "X7") (pin "4") (pinfunction "4_4") (pintype "passive"))
    )
    (net (code "140") (name "SPI_SCK") (class "Default")
      (node (ref "IC2") (pin "21") (pinfunction "PA5_21") (pintype "bidirectional"))
      (node (ref "X7") (pin "3") (pinfunction "3_3") (pintype "passive"))
    )
    (net (code "141") (name "SWCLK") (class "Default")
      (node (ref "IC2") (pin "49") (pinfunction "PA14_49") (pintype "bidirectional"))
      (node (ref "SL1") (pin "2") (pinfunction "2_2") (pintype "passive"))
    )
    (net (code "142") (name "SWDIO") (class "Default")
      (node (ref "IC2") (pin "46") (pinfunction "PA13_46") (pintype "bidirectional"))
      (node (ref "SL1") (pin "4") (pinfunction "4_4") (pintype "passive"))
    )
    (net (code "143") (name "USART_RX") (class "Default")
      (node (ref "IC2") (pin "29") (pinfunction "PB11_29") (pintype "bidirectional"))
      (node (ref "X8") (pin "2") (pinfunction "2_2") (pintype "passive"))
    )
    (net (code "144") (name "USRAT_TX") (class "Default")
      (node (ref "IC2") (pin "28") (pinfunction "PB10_28") (pintype "bidirectional"))
      (node (ref "X8") (pin "1") (pinfunction "1_1") (pintype "passive"))
    )
    (net (code "145") (name "VCAP_1") (class "Default")
      (node (ref "C20") (pin "2") (pinfunction "2_2") (pintype "bidirectional"))
      (node (ref "C21") (pin "2") (pinfunction "2_2") (pintype "bidirectional"))
      (node (ref "IC2") (pin "30") (pinfunction "VCAP_1_30") (pintype "power_in"))
    )
    (net (code "146") (name "unconnected-(IC2-PA10-Pad43)") (class "Default")
      (node (ref "IC2") (pin "43") (pinfunction "PA10_43") (pintype "bidirectional"))
    )
    (net (code "147") (name "unconnected-(IC2-PB12-Pad33)") (class "Default")
      (node (ref "IC2") (pin "33") (pinfunction "PB12_33") (pintype "bidirectional"))
    )
    (net (code "148") (name "unconnected-(IC2-PB13-Pad34)") (class "Default")
      (node (ref "IC2") (pin "34") (pinfunction "PB13_34") (pintype "bidirectional"))
    )
    (net (code "149") (name "unconnected-(IC2-PH0-OSC_IN-Pad5)") (class "Default")
      (node (ref "IC2") (pin "5") (pinfunction "PH0-OSC_IN_5") (pintype "bidirectional"))
    )
    (net (code "150") (name "unconnected-(IC2-PH1-OSC_OUT-Pad6)") (class "Default")
      (node (ref "IC2") (pin "6") (pinfunction "PH1-OSC_OUT_6") (pintype "bidirectional"))
    )
    (net (code "151") (name "unconnected-(J2-PadMH1)") (class "Default")
      (node (ref "J2") (pin "MH1") (pinfunction "MH1_MH1") (pintype "bidirectional"))
    )
    (net (code "152") (name "unconnected-(J2-PadMH2)") (class "Default")
      (node (ref "J2") (pin "MH2") (pinfunction "MH2_MH2") (pintype "bidirectional"))
    )
    (net (code "153") (name "unconnected-(J2-PadMH3)") (class "Default")
      (node (ref "J2") (pin "MH3") (pinfunction "MH3_MH3") (pintype "bidirectional"))
    )
    (net (code "154") (name "unconnected-(J2-PadMH4)") (class "Default")
      (node (ref "J2") (pin "MH4") (pinfunction "MH4_MH4") (pintype "bidirectional"))
    )
    (net (code "155") (name "unconnected-(S1-COM_2-PadD1)") (class "Default")
      (node (ref "S1") (pin "D1") (pinfunction "COM_2_D1") (pintype "bidirectional"))
    )
    (net (code "156") (name "unconnected-(S1-NO_2-PadB1)") (class "Default")
      (node (ref "S1") (pin "B1") (pinfunction "NO_2_B1") (pintype "bidirectional"))
    )
    (net (code "157") (name "unconnected-(S2-NO_2-PadB1)") (class "Default")
      (node (ref "S2") (pin "B1") (pinfunction "NO_2_B1") (pintype "bidirectional"))
    )
    (net (code "158") (name "unconnected-(SL1-Pad6)") (class "Default")
      (node (ref "SL1") (pin "6") (pinfunction "6_6") (pintype "passive"))
    )
    (net (code "159") (name "unconnected-(X1-Pad2)") (class "Default")
      (node (ref "X1") (pin "2") (pinfunction "2_2") (pintype "passive"))
    )
    (net (code "160") (name "unconnected-(X2-Pad2)") (class "Default")
      (node (ref "X2") (pin "2") (pinfunction "2_2") (pintype "passive"))
    )
    (net (code "161") (name "unconnected-(X5-Pad2)") (class "Default")
      (node (ref "X5") (pin "2") (pinfunction "2_2") (pintype "passive"))
    )
    (net (code "162") (name "unconnected-(X6-Pad2)") (class "Default")
      (node (ref "X6") (pin "2") (pinfunction "2_2") (pintype "passive"))
    )
  )
)
